# protoplank.net
KiCad netlist of a schematic drawn in EAGLE
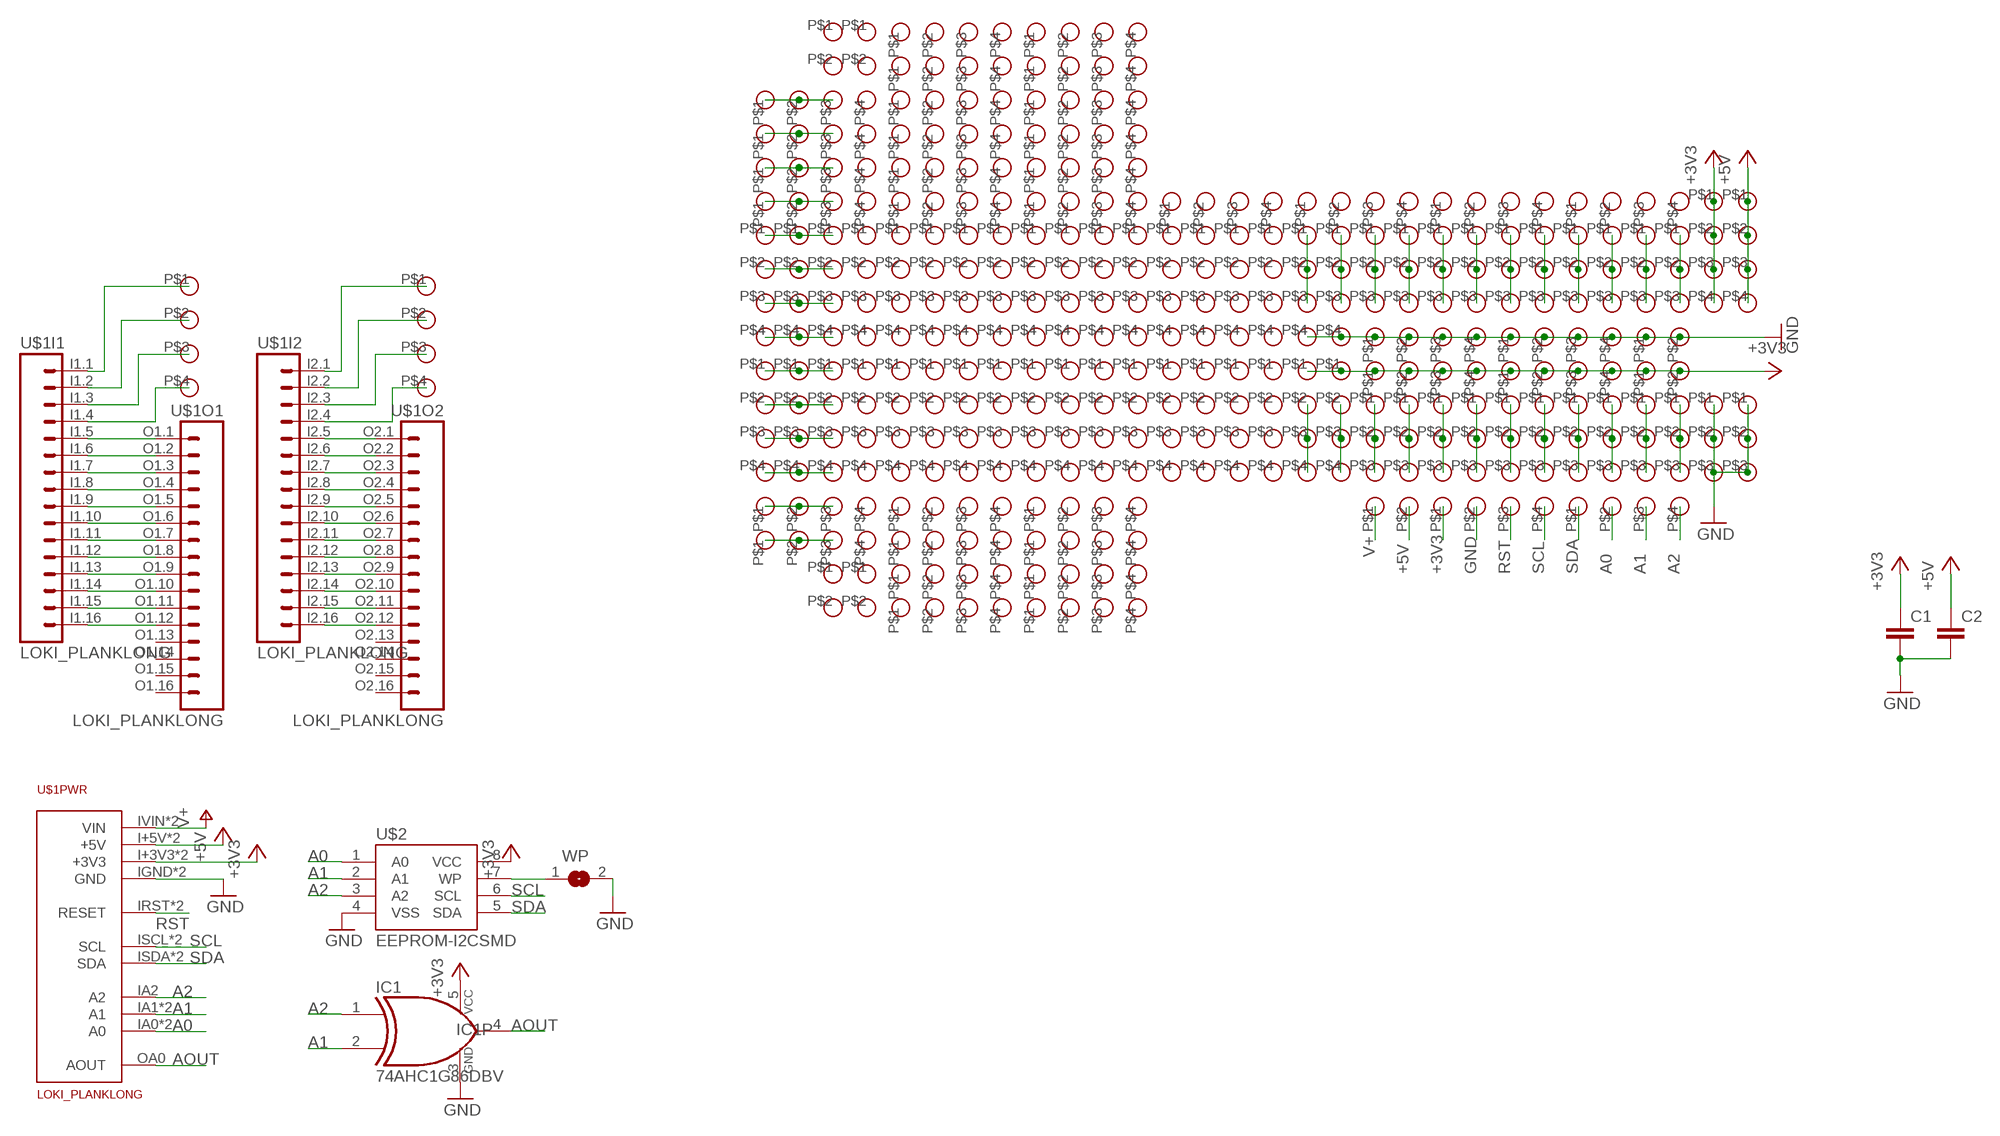
[diagram p0: schematic, sheet 1]

(export (version "E")
  (design (tool "Eeschema 10.0.6"))
  (components
    (comp (ref "C1")
      (value "CAPPTH")
      (footprint "eagle-import:CAP-PTH-SMALL")
      (libsource (lib "eagle-import") (part "CAPPTH"))
    )
    (comp (ref "C2")
      (value "CAPPTH")
      (footprint "eagle-import:CAP-PTH-SMALL")
      (libsource (lib "eagle-import") (part "CAPPTH"))
    )
    (comp (ref "IC1")
      (value "74AHC1G86DBV")
      (footprint "eagle-import:SOT23-5")
      (libsource (lib "eagle-import") (part "741G86DBVAHC"))
    )
    (comp (ref "U$1")
      (value "LOKI_PLANKLONG")
      (footprint "eagle-import:PLANK_LONG")
      (libsource (lib "eagle-import") (part "LOKI_PLANKLONG"))
    )
    (comp (ref "U$2")
      (value "EEPROM-I2CSMD")
      (footprint "eagle-import:SO08")
      (libsource (lib "eagle-import") (part "EEPROM-I2CSMD"))
    )
    (comp (ref "U$3")
      (value "PROTOPAD-3")
      (footprint "eagle-import:PROTOPAD-3")
      (libsource (lib "eagle-import") (part "PROTOPAD-3"))
    )
    (comp (ref "U$4")
      (value "PROTOPAD-3")
      (footprint "eagle-import:PROTOPAD-3")
      (libsource (lib "eagle-import") (part "PROTOPAD-3"))
    )
    (comp (ref "U$5")
      (value "PROTOPAD-3")
      (footprint "eagle-import:PROTOPAD-3")
      (libsource (lib "eagle-import") (part "PROTOPAD-3"))
    )
    (comp (ref "U$6")
      (value "PROTOPAD-3")
      (footprint "eagle-import:PROTOPAD-3")
      (libsource (lib "eagle-import") (part "PROTOPAD-3"))
    )
    (comp (ref "U$7")
      (value "PROTOPAD-3")
      (footprint "eagle-import:PROTOPAD-3")
      (libsource (lib "eagle-import") (part "PROTOPAD-3"))
    )
    (comp (ref "U$8")
      (value "PROTOPAD-3")
      (footprint "eagle-import:PROTOPAD-3")
      (libsource (lib "eagle-import") (part "PROTOPAD-3"))
    )
    (comp (ref "U$9")
      (value "PROTOPAD-3")
      (footprint "eagle-import:PROTOPAD-3")
      (libsource (lib "eagle-import") (part "PROTOPAD-3"))
    )
    (comp (ref "U$10")
      (value "PROTOPAD-3")
      (footprint "eagle-import:PROTOPAD-3")
      (libsource (lib "eagle-import") (part "PROTOPAD-3"))
    )
    (comp (ref "U$11")
      (value "PROTOPAD-3")
      (footprint "eagle-import:PROTOPAD-3")
      (libsource (lib "eagle-import") (part "PROTOPAD-3"))
    )
    (comp (ref "U$12")
      (value "PROTOPAD-3")
      (footprint "eagle-import:PROTOPAD-3")
      (libsource (lib "eagle-import") (part "PROTOPAD-3"))
    )
    (comp (ref "U$13")
      (value "PROTOPAD-3")
      (footprint "eagle-import:PROTOPAD-3")
      (libsource (lib "eagle-import") (part "PROTOPAD-3"))
    )
    (comp (ref "U$14")
      (value "PROTOPAD-3")
      (footprint "eagle-import:PROTOPAD-3")
      (libsource (lib "eagle-import") (part "PROTOPAD-3"))
    )
    (comp (ref "U$15")
      (value "PROTOPAD-3")
      (footprint "eagle-import:PROTOPAD-3")
      (libsource (lib "eagle-import") (part "PROTOPAD-3"))
    )
    (comp (ref "U$16")
      (value "PROTOPAD-3")
      (footprint "eagle-import:PROTOPAD-3")
      (libsource (lib "eagle-import") (part "PROTOPAD-3"))
    )
    (comp (ref "U$17")
      (value "PROTOPAD-3")
      (footprint "eagle-import:PROTOPAD-3")
      (libsource (lib "eagle-import") (part "PROTOPAD-3"))
    )
    (comp (ref "U$18")
      (value "PROTOPAD-3")
      (footprint "eagle-import:PROTOPAD-3")
      (libsource (lib "eagle-import") (part "PROTOPAD-3"))
    )
    (comp (ref "U$19")
      (value "PROTOPAD-3")
      (footprint "eagle-import:PROTOPAD-3")
      (libsource (lib "eagle-import") (part "PROTOPAD-3"))
    )
    (comp (ref "U$20")
      (value "PROTOPAD-3")
      (footprint "eagle-import:PROTOPAD-3")
      (libsource (lib "eagle-import") (part "PROTOPAD-3"))
    )
    (comp (ref "U$21")
      (value "PROTOPAD-3")
      (footprint "eagle-import:PROTOPAD-3")
      (libsource (lib "eagle-import") (part "PROTOPAD-3"))
    )
    (comp (ref "U$22")
      (value "PROTOPAD-3")
      (footprint "eagle-import:PROTOPAD-3")
      (libsource (lib "eagle-import") (part "PROTOPAD-3"))
    )
    (comp (ref "U$23")
      (value "PROTOPAD-4SQUARE")
      (footprint "eagle-import:PROTOPAD-4")
      (libsource (lib "eagle-import") (part "PROTOPAD-4SQUARE"))
    )
    (comp (ref "U$24")
      (value "PROTOPAD-4SQUARE")
      (footprint "eagle-import:PROTOPAD-4")
      (libsource (lib "eagle-import") (part "PROTOPAD-4SQUARE"))
    )
    (comp (ref "U$25")
      (value "PROTOPAD-4SQUARE")
      (footprint "eagle-import:PROTOPAD-4")
      (libsource (lib "eagle-import") (part "PROTOPAD-4SQUARE"))
    )
    (comp (ref "U$26")
      (value "PROTOPAD-4SQUARE")
      (footprint "eagle-import:PROTOPAD-4")
      (libsource (lib "eagle-import") (part "PROTOPAD-4SQUARE"))
    )
    (comp (ref "U$27")
      (value "PROTOPAD-2SQUARE")
      (footprint "eagle-import:PROTOPAD-2")
      (libsource (lib "eagle-import") (part "PROTOPAD-2SQUARE"))
    )
    (comp (ref "U$28")
      (value "PROTOPAD-2SQUARE")
      (footprint "eagle-import:PROTOPAD-2")
      (libsource (lib "eagle-import") (part "PROTOPAD-2SQUARE"))
    )
    (comp (ref "U$29")
      (value "PROTOPAD-4ROUND")
      (footprint "eagle-import:PROTOPAD-4-ROUND")
      (libsource (lib "eagle-import") (part "PROTOPAD-4ROUND"))
    )
    (comp (ref "U$30")
      (value "PROTOPAD-4ROUND")
      (footprint "eagle-import:PROTOPAD-4-ROUND")
      (libsource (lib "eagle-import") (part "PROTOPAD-4ROUND"))
    )
    (comp (ref "U$31")
      (value "PROTOPAD-4ROUND")
      (footprint "eagle-import:PROTOPAD-4-ROUND")
      (libsource (lib "eagle-import") (part "PROTOPAD-4ROUND"))
    )
    (comp (ref "U$32")
      (value "PROTOPAD-4ROUND")
      (footprint "eagle-import:PROTOPAD-4-ROUND")
      (libsource (lib "eagle-import") (part "PROTOPAD-4ROUND"))
    )
    (comp (ref "U$33")
      (value "PROTOPAD-2ROUND")
      (footprint "eagle-import:PROTOPAD-2-ROUND")
      (libsource (lib "eagle-import") (part "PROTOPAD-2ROUND"))
    )
    (comp (ref "U$34")
      (value "PROTOPAD-4SQUARE")
      (footprint "eagle-import:PROTOPAD-4")
      (libsource (lib "eagle-import") (part "PROTOPAD-4SQUARE"))
    )
    (comp (ref "U$35")
      (value "PROTOPAD-4SQUARE")
      (footprint "eagle-import:PROTOPAD-4")
      (libsource (lib "eagle-import") (part "PROTOPAD-4SQUARE"))
    )
    (comp (ref "U$36")
      (value "PROTOPAD-4SQUARE")
      (footprint "eagle-import:PROTOPAD-4")
      (libsource (lib "eagle-import") (part "PROTOPAD-4SQUARE"))
    )
    (comp (ref "U$37")
      (value "PROTOPAD-4SQUARE")
      (footprint "eagle-import:PROTOPAD-4")
      (libsource (lib "eagle-import") (part "PROTOPAD-4SQUARE"))
    )
    (comp (ref "U$38")
      (value "PROTOPAD-4SQUARE")
      (footprint "eagle-import:PROTOPAD-4")
      (libsource (lib "eagle-import") (part "PROTOPAD-4SQUARE"))
    )
    (comp (ref "U$39")
      (value "PROTOPAD-4SQUARE")
      (footprint "eagle-import:PROTOPAD-4")
      (libsource (lib "eagle-import") (part "PROTOPAD-4SQUARE"))
    )
    (comp (ref "U$40")
      (value "PROTOPAD-4SQUARE")
      (footprint "eagle-import:PROTOPAD-4")
      (libsource (lib "eagle-import") (part "PROTOPAD-4SQUARE"))
    )
    (comp (ref "U$41")
      (value "PROTOPAD-4SQUARE")
      (footprint "eagle-import:PROTOPAD-4")
      (libsource (lib "eagle-import") (part "PROTOPAD-4SQUARE"))
    )
    (comp (ref "U$42")
      (value "PROTOPAD-4SQUARE")
      (footprint "eagle-import:PROTOPAD-4")
      (libsource (lib "eagle-import") (part "PROTOPAD-4SQUARE"))
    )
    (comp (ref "U$43")
      (value "PROTOPAD-4SQUARE")
      (footprint "eagle-import:PROTOPAD-4")
      (libsource (lib "eagle-import") (part "PROTOPAD-4SQUARE"))
    )
    (comp (ref "U$44")
      (value "PROTOPAD-4SQUARE")
      (footprint "eagle-import:PROTOPAD-4")
      (libsource (lib "eagle-import") (part "PROTOPAD-4SQUARE"))
    )
    (comp (ref "U$45")
      (value "PROTOPAD-4SQUARE")
      (footprint "eagle-import:PROTOPAD-4")
      (libsource (lib "eagle-import") (part "PROTOPAD-4SQUARE"))
    )
    (comp (ref "U$46")
      (value "PROTOPAD-4SQUARE")
      (footprint "eagle-import:PROTOPAD-4")
      (libsource (lib "eagle-import") (part "PROTOPAD-4SQUARE"))
    )
    (comp (ref "U$47")
      (value "PROTOPAD-4SQUARE")
      (footprint "eagle-import:PROTOPAD-4")
      (libsource (lib "eagle-import") (part "PROTOPAD-4SQUARE"))
    )
    (comp (ref "U$48")
      (value "PROTOPAD-4SQUARE")
      (footprint "eagle-import:PROTOPAD-4")
      (libsource (lib "eagle-import") (part "PROTOPAD-4SQUARE"))
    )
    (comp (ref "U$49")
      (value "PROTOPAD-4SQUARE")
      (footprint "eagle-import:PROTOPAD-4")
      (libsource (lib "eagle-import") (part "PROTOPAD-4SQUARE"))
    )
    (comp (ref "U$50")
      (value "PROTOPAD-4SQUARE")
      (footprint "eagle-import:PROTOPAD-4")
      (libsource (lib "eagle-import") (part "PROTOPAD-4SQUARE"))
    )
    (comp (ref "U$51")
      (value "PROTOPAD-4SQUARE")
      (footprint "eagle-import:PROTOPAD-4")
      (libsource (lib "eagle-import") (part "PROTOPAD-4SQUARE"))
    )
    (comp (ref "U$52")
      (value "PROTOPAD-4SQUARE")
      (footprint "eagle-import:PROTOPAD-4")
      (libsource (lib "eagle-import") (part "PROTOPAD-4SQUARE"))
    )
    (comp (ref "U$53")
      (value "PROTOPAD-4SQUARE")
      (footprint "eagle-import:PROTOPAD-4")
      (libsource (lib "eagle-import") (part "PROTOPAD-4SQUARE"))
    )
    (comp (ref "U$54")
      (value "PROTOPAD-4SQUARE")
      (footprint "eagle-import:PROTOPAD-4")
      (libsource (lib "eagle-import") (part "PROTOPAD-4SQUARE"))
    )
    (comp (ref "U$55")
      (value "PROTOPAD-4SQUARE")
      (footprint "eagle-import:PROTOPAD-4")
      (libsource (lib "eagle-import") (part "PROTOPAD-4SQUARE"))
    )
    (comp (ref "U$56")
      (value "PROTOPAD-4SQUARE")
      (footprint "eagle-import:PROTOPAD-4")
      (libsource (lib "eagle-import") (part "PROTOPAD-4SQUARE"))
    )
    (comp (ref "U$57")
      (value "PROTOPAD-4SQUARE")
      (footprint "eagle-import:PROTOPAD-4")
      (libsource (lib "eagle-import") (part "PROTOPAD-4SQUARE"))
    )
    (comp (ref "U$58")
      (value "PROTOPAD-4SQUARE")
      (footprint "eagle-import:PROTOPAD-4")
      (libsource (lib "eagle-import") (part "PROTOPAD-4SQUARE"))
    )
    (comp (ref "U$59")
      (value "PROTOPAD-4SQUARE")
      (footprint "eagle-import:PROTOPAD-4")
      (libsource (lib "eagle-import") (part "PROTOPAD-4SQUARE"))
    )
    (comp (ref "U$60")
      (value "PROTOPAD-4SQUARE")
      (footprint "eagle-import:PROTOPAD-4")
      (libsource (lib "eagle-import") (part "PROTOPAD-4SQUARE"))
    )
    (comp (ref "U$61")
      (value "PROTOPAD-4SQUARE")
      (footprint "eagle-import:PROTOPAD-4")
      (libsource (lib "eagle-import") (part "PROTOPAD-4SQUARE"))
    )
    (comp (ref "U$62")
      (value "PROTOPAD-4SQUARE")
      (footprint "eagle-import:PROTOPAD-4")
      (libsource (lib "eagle-import") (part "PROTOPAD-4SQUARE"))
    )
    (comp (ref "U$63")
      (value "PROTOPAD-4SQUARE")
      (footprint "eagle-import:PROTOPAD-4")
      (libsource (lib "eagle-import") (part "PROTOPAD-4SQUARE"))
    )
    (comp (ref "U$64")
      (value "PROTOPAD-4SQUARE")
      (footprint "eagle-import:PROTOPAD-4")
      (libsource (lib "eagle-import") (part "PROTOPAD-4SQUARE"))
    )
    (comp (ref "U$65")
      (value "PROTOPAD-4SQUARE")
      (footprint "eagle-import:PROTOPAD-4")
      (libsource (lib "eagle-import") (part "PROTOPAD-4SQUARE"))
    )
    (comp (ref "U$66")
      (value "PROTOPAD-4SQUARE")
      (footprint "eagle-import:PROTOPAD-4")
      (libsource (lib "eagle-import") (part "PROTOPAD-4SQUARE"))
    )
    (comp (ref "U$67")
      (value "PROTOPAD-4SQUARE")
      (footprint "eagle-import:PROTOPAD-4")
      (libsource (lib "eagle-import") (part "PROTOPAD-4SQUARE"))
    )
    (comp (ref "U$68")
      (value "PROTOPAD-4SQUARE")
      (footprint "eagle-import:PROTOPAD-4")
      (libsource (lib "eagle-import") (part "PROTOPAD-4SQUARE"))
    )
    (comp (ref "U$69")
      (value "PROTOPAD-4SQUARE")
      (footprint "eagle-import:PROTOPAD-4")
      (libsource (lib "eagle-import") (part "PROTOPAD-4SQUARE"))
    )
    (comp (ref "U$70")
      (value "PROTOPAD-4SQUARE")
      (footprint "eagle-import:PROTOPAD-4")
      (libsource (lib "eagle-import") (part "PROTOPAD-4SQUARE"))
    )
    (comp (ref "U$71")
      (value "PROTOPAD-4SQUARE")
      (footprint "eagle-import:PROTOPAD-4")
      (libsource (lib "eagle-import") (part "PROTOPAD-4SQUARE"))
    )
    (comp (ref "U$72")
      (value "PROTOPAD-4SQUARE")
      (footprint "eagle-import:PROTOPAD-4")
      (libsource (lib "eagle-import") (part "PROTOPAD-4SQUARE"))
    )
    (comp (ref "U$73")
      (value "PROTOPAD-4SQUARE")
      (footprint "eagle-import:PROTOPAD-4")
      (libsource (lib "eagle-import") (part "PROTOPAD-4SQUARE"))
    )
    (comp (ref "U$74")
      (value "PROTOPAD-4SQUARE")
      (footprint "eagle-import:PROTOPAD-4")
      (libsource (lib "eagle-import") (part "PROTOPAD-4SQUARE"))
    )
    (comp (ref "U$75")
      (value "PROTOPAD-4SQUARE")
      (footprint "eagle-import:PROTOPAD-4")
      (libsource (lib "eagle-import") (part "PROTOPAD-4SQUARE"))
    )
    (comp (ref "U$76")
      (value "PROTOPAD-4SQUARE")
      (footprint "eagle-import:PROTOPAD-4")
      (libsource (lib "eagle-import") (part "PROTOPAD-4SQUARE"))
    )
    (comp (ref "U$77")
      (value "PROTOPAD-4SQUARE")
      (footprint "eagle-import:PROTOPAD-4")
      (libsource (lib "eagle-import") (part "PROTOPAD-4SQUARE"))
    )
    (comp (ref "U$78")
      (value "PROTOPAD-3")
      (footprint "eagle-import:PROTOPAD-3")
      (libsource (lib "eagle-import") (part "PROTOPAD-3"))
    )
    (comp (ref "U$79")
      (value "PROTOPAD-4SQUARE")
      (footprint "eagle-import:PROTOPAD-4")
      (libsource (lib "eagle-import") (part "PROTOPAD-4SQUARE"))
    )
    (comp (ref "U$80")
      (value "PROTOPAD-3")
      (footprint "eagle-import:PROTOPAD-3")
      (libsource (lib "eagle-import") (part "PROTOPAD-3"))
    )
    (comp (ref "U$81")
      (value "PROTOPAD-4SQUARE")
      (footprint "eagle-import:PROTOPAD-4")
      (libsource (lib "eagle-import") (part "PROTOPAD-4SQUARE"))
    )
    (comp (ref "U$82")
      (value "PROTOPAD-4SQUARE")
      (footprint "eagle-import:PROTOPAD-4")
      (libsource (lib "eagle-import") (part "PROTOPAD-4SQUARE"))
    )
    (comp (ref "U$83")
      (value "PROTOPAD-4SQUARE")
      (footprint "eagle-import:PROTOPAD-4")
      (libsource (lib "eagle-import") (part "PROTOPAD-4SQUARE"))
    )
    (comp (ref "U$84")
      (value "PROTOPAD-4SQUARE")
      (footprint "eagle-import:PROTOPAD-4")
      (libsource (lib "eagle-import") (part "PROTOPAD-4SQUARE"))
    )
    (comp (ref "U$85")
      (value "PROTOPAD-4SQUARE")
      (footprint "eagle-import:PROTOPAD-4")
      (libsource (lib "eagle-import") (part "PROTOPAD-4SQUARE"))
    )
    (comp (ref "U$86")
      (value "PROTOPAD-4SQUARE")
      (footprint "eagle-import:PROTOPAD-4")
      (libsource (lib "eagle-import") (part "PROTOPAD-4SQUARE"))
    )
    (comp (ref "U$87")
      (value "PROTOPAD-4SQUARE")
      (footprint "eagle-import:PROTOPAD-4")
      (libsource (lib "eagle-import") (part "PROTOPAD-4SQUARE"))
    )
    (comp (ref "U$88")
      (value "PROTOPAD-4SQUARE")
      (footprint "eagle-import:PROTOPAD-4")
      (libsource (lib "eagle-import") (part "PROTOPAD-4SQUARE"))
    )
    (comp (ref "U$89")
      (value "PROTOPAD-4SQUARE")
      (footprint "eagle-import:PROTOPAD-4")
      (libsource (lib "eagle-import") (part "PROTOPAD-4SQUARE"))
    )
    (comp (ref "U$90")
      (value "PROTOPAD-4SQUARE")
      (footprint "eagle-import:PROTOPAD-4")
      (libsource (lib "eagle-import") (part "PROTOPAD-4SQUARE"))
    )
    (comp (ref "U$91")
      (value "PROTOPAD-4SQUARE")
      (footprint "eagle-import:PROTOPAD-4")
      (libsource (lib "eagle-import") (part "PROTOPAD-4SQUARE"))
    )
    (comp (ref "U$92")
      (value "PROTOPAD-4SQUARE")
      (footprint "eagle-import:PROTOPAD-4")
      (libsource (lib "eagle-import") (part "PROTOPAD-4SQUARE"))
    )
    (comp (ref "U$93")
      (value "PROTOPAD-4SQUARE")
      (footprint "eagle-import:PROTOPAD-4")
      (libsource (lib "eagle-import") (part "PROTOPAD-4SQUARE"))
    )
    (comp (ref "U$94")
      (value "PROTOPAD-4SQUARE")
      (footprint "eagle-import:PROTOPAD-4")
      (libsource (lib "eagle-import") (part "PROTOPAD-4SQUARE"))
    )
    (comp (ref "U$95")
      (value "PROTOPAD-4SQUARE")
      (footprint "eagle-import:PROTOPAD-4")
      (libsource (lib "eagle-import") (part "PROTOPAD-4SQUARE"))
    )
    (comp (ref "U$96")
      (value "PROTOPAD-4SQUARE")
      (footprint "eagle-import:PROTOPAD-4")
      (libsource (lib "eagle-import") (part "PROTOPAD-4SQUARE"))
    )
    (comp (ref "U$97")
      (value "PROTOPAD-4SQUARE")
      (footprint "eagle-import:PROTOPAD-4")
      (libsource (lib "eagle-import") (part "PROTOPAD-4SQUARE"))
    )
    (comp (ref "U$98")
      (value "PROTOPAD-4SQUARE")
      (footprint "eagle-import:PROTOPAD-4")
      (libsource (lib "eagle-import") (part "PROTOPAD-4SQUARE"))
    )
    (comp (ref "U$99")
      (value "PROTOPAD-4SQUARE")
      (footprint "eagle-import:PROTOPAD-4")
      (libsource (lib "eagle-import") (part "PROTOPAD-4SQUARE"))
    )
    (comp (ref "U$100")
      (value "PROTOPAD-4SQUARE")
      (footprint "eagle-import:PROTOPAD-4")
      (libsource (lib "eagle-import") (part "PROTOPAD-4SQUARE"))
    )
    (comp (ref "U$101")
      (value "PROTOPAD-4SQUARE")
      (footprint "eagle-import:PROTOPAD-4")
      (libsource (lib "eagle-import") (part "PROTOPAD-4SQUARE"))
    )
    (comp (ref "U$102")
      (value "PROTOPAD-4SQUARE")
      (footprint "eagle-import:PROTOPAD-4")
      (libsource (lib "eagle-import") (part "PROTOPAD-4SQUARE"))
    )
    (comp (ref "U$103")
      (value "PROTOPAD-4SQUARE")
      (footprint "eagle-import:PROTOPAD-4")
      (libsource (lib "eagle-import") (part "PROTOPAD-4SQUARE"))
    )
    (comp (ref "U$104")
      (value "PROTOPAD-2SQUARE")
      (footprint "eagle-import:PROTOPAD-2")
      (libsource (lib "eagle-import") (part "PROTOPAD-2SQUARE"))
    )
    (comp (ref "U$105")
      (value "PROTOPAD-2SQUARE")
      (footprint "eagle-import:PROTOPAD-2")
      (libsource (lib "eagle-import") (part "PROTOPAD-2SQUARE"))
    )
    (comp (ref "U$106")
      (value "PROTOPAD-2SQUARE")
      (footprint "eagle-import:PROTOPAD-2")
      (libsource (lib "eagle-import") (part "PROTOPAD-2SQUARE"))
    )
    (comp (ref "U$107")
      (value "PROTOPAD-2SQUARE")
      (footprint "eagle-import:PROTOPAD-2")
      (libsource (lib "eagle-import") (part "PROTOPAD-2SQUARE"))
    )
    (comp (ref "WP") (value "SJ") (footprint "eagle-import:SJ") (libsource (lib "eagle-import") (part "SJ")))
  )
  (nets
    (net (code "1") (name "+3V3") (class "Default")
      (node (ref "C1") (pin "1") (pinfunction "1_1") (pintype "passive"))
      (node (ref "IC1") (pin "5") (pinfunction "VCC_5") (pintype "power_in"))
      (node (ref "U$1") (pin "I+3V3") (pinfunction "+3V3_I+3V3") (pintype "power_in"))
      (node (ref "U$1") (pin "O+3V3") (pinfunction "+3V3_O+3V3") (pintype "power_in"))
      (node (ref "U$2") (pin "8") (pinfunction "VCC_8") (pintype "power_in"))
      (node (ref "U$25") (pin "P$1") (pinfunction "P$1_P$1") (pintype "passive"))
      (node (ref "U$25") (pin "P$2") (pinfunction "P$2_P$2") (pintype "passive"))
      (node (ref "U$25") (pin "P$3") (pinfunction "P$3_P$3") (pintype "passive"))
      (node (ref "U$25") (pin "P$4") (pinfunction "P$4_P$4") (pintype "passive"))
      (node (ref "U$26") (pin "P$1") (pinfunction "P$1_P$1") (pintype "passive"))
      (node (ref "U$26") (pin "P$2") (pinfunction "P$2_P$2") (pintype "passive"))
      (node (ref "U$26") (pin "P$3") (pinfunction "P$3_P$3") (pintype "passive"))
      (node (ref "U$26") (pin "P$4") (pinfunction "P$4_P$4") (pintype "passive"))
      (node (ref "U$28") (pin "P$1") (pinfunction "P$1_P$1") (pintype "passive"))
      (node (ref "U$28") (pin "P$2") (pinfunction "P$2_P$2") (pintype "passive"))
      (node (ref "U$32") (pin "P$1") (pinfunction "P$1_P$1") (pintype "passive"))
      (node (ref "U$35") (pin "P$1") (pinfunction "P$1_P$1") (pintype "passive"))
      (node (ref "U$36") (pin "P$1") (pinfunction "P$1_P$1") (pintype "passive"))
      (node (ref "U$77") (pin "P$1") (pinfunction "P$1_P$1") (pintype "passive"))
      (node (ref "U$77") (pin "P$2") (pinfunction "P$2_P$2") (pintype "passive"))
      (node (ref "U$77") (pin "P$3") (pinfunction "P$3_P$3") (pintype "passive"))
      (node (ref "U$77") (pin "P$4") (pinfunction "P$4_P$4") (pintype "passive"))
    )
    (net (code "2") (name "+5V") (class "Default")
      (node (ref "C2") (pin "1") (pinfunction "1_1") (pintype "passive"))
      (node (ref "U$1") (pin "I+5V") (pinfunction "+5V_I+5V") (pintype "power_in"))
      (node (ref "U$1") (pin "O+5V") (pinfunction "+5V_O+5V") (pintype "power_in"))
      (node (ref "U$33") (pin "P$2") (pinfunction "P$2_P$2") (pintype "passive"))
      (node (ref "U$79") (pin "P$1") (pinfunction "P$1_P$1") (pintype "passive"))
      (node (ref "U$79") (pin "P$2") (pinfunction "P$2_P$2") (pintype "passive"))
      (node (ref "U$79") (pin "P$3") (pinfunction "P$3_P$3") (pintype "passive"))
      (node (ref "U$79") (pin "P$4") (pinfunction "P$4_P$4") (pintype "passive"))
    )
    (net (code "3") (name "/A0") (class "Default")
      (node (ref "U$1") (pin "IA0") (pinfunction "A0_IA0") (pintype "output"))
      (node (ref "U$1") (pin "OA1") (pinfunction "A0_OA1") (pintype "output"))
      (node (ref "U$2") (pin "1") (pinfunction "A0_1") (pintype "bidirectional"))
      (node (ref "U$31") (pin "P$2") (pinfunction "P$2_P$2") (pintype "passive"))
    )
    (net (code "4") (name "/A1") (class "Default")
      (node (ref "IC1") (pin "2") (pinfunction "I1_2") (pintype "input"))
      (node (ref "U$1") (pin "IA1") (pinfunction "A1_IA1") (pintype "output"))
      (node (ref "U$1") (pin "OA2") (pinfunction "A1_OA2") (pintype "output"))
      (node (ref "U$2") (pin "2") (pinfunction "A1_2") (pintype "bidirectional"))
      (node (ref "U$31") (pin "P$3") (pinfunction "P$3_P$3") (pintype "passive"))
    )
    (net (code "5") (name "/A2") (class "Default")
      (node (ref "IC1") (pin "1") (pinfunction "I0_1") (pintype "input"))
      (node (ref "U$1") (pin "IA2") (pinfunction "A2_IA2") (pintype "output"))
      (node (ref "U$2") (pin "3") (pinfunction "A2_3") (pintype "bidirectional"))
      (node (ref "U$31") (pin "P$4") (pinfunction "P$4_P$4") (pintype "passive"))
    )
    (net (code "6") (name "/AOUT") (class "Default")
      (node (ref "IC1") (pin "4") (pinfunction "O_4") (pintype "output"))
      (node (ref "U$1") (pin "OA0") (pinfunction "AOUT_OA0") (pintype "input"))
    )
    (net (code "7") (name "/RST") (class "Default")
      (node (ref "U$1") (pin "IRST") (pinfunction "RESET_IRST") (pintype "input"))
      (node (ref "U$1") (pin "ORST") (pinfunction "RESET_ORST") (pintype "input"))
      (node (ref "U$32") (pin "P$3") (pinfunction "P$3_P$3") (pintype "passive"))
    )
    (net (code "8") (name "/SCL") (class "Default")
      (node (ref "U$1") (pin "ISCL") (pinfunction "SCL_ISCL") (pintype "bidirectional"))
      (node (ref "U$1") (pin "OSCL") (pinfunction "SCL_OSCL") (pintype "bidirectional"))
      (node (ref "U$2") (pin "6") (pinfunction "SCL_6") (pintype "bidirectional"))
      (node (ref "U$32") (pin "P$4") (pinfunction "P$4_P$4") (pintype "passive"))
    )
    (net (code "9") (name "/SDA") (class "Default")
      (node (ref "U$1") (pin "ISDA") (pinfunction "SDA_ISDA") (pintype "bidirectional"))
      (node (ref "U$1") (pin "OSDA") (pinfunction "SDA_OSDA") (pintype "bidirectional"))
      (node (ref "U$2") (pin "5") (pinfunction "SDA_5") (pintype "bidirectional"))
      (node (ref "U$31") (pin "P$1") (pinfunction "P$1_P$1") (pintype "passive"))
    )
    (net (code "10") (name "GND") (class "Default")
      (node (ref "C1") (pin "2") (pinfunction "2_2") (pintype "passive"))
      (node (ref "C2") (pin "2") (pinfunction "2_2") (pintype "passive"))
      (node (ref "IC1") (pin "3") (pinfunction "GND_3") (pintype "power_in"))
      (node (ref "U$1") (pin "IGND") (pinfunction "GND_IGND") (pintype "power_in"))
      (node (ref "U$1") (pin "OGND") (pinfunction "GND_OGND") (pintype "power_in"))
      (node (ref "U$2") (pin "4") (pinfunction "VSS_4") (pintype "power_in"))
      (node (ref "U$23") (pin "P$1") (pinfunction "P$1_P$1") (pintype "passive"))
      (node (ref "U$23") (pin "P$2") (pinfunction "P$2_P$2") (pintype "passive"))
      (node (ref "U$23") (pin "P$3") (pinfunction "P$3_P$3") (pintype "passive"))
      (node (ref "U$23") (pin "P$4") (pinfunction "P$4_P$4") (pintype "passive"))
      (node (ref "U$24") (pin "P$1") (pinfunction "P$1_P$1") (pintype "passive"))
      (node (ref "U$24") (pin "P$2") (pinfunction "P$2_P$2") (pintype "passive"))
      (node (ref "U$24") (pin "P$3") (pinfunction "P$3_P$3") (pintype "passive"))
      (node (ref "U$24") (pin "P$4") (pinfunction "P$4_P$4") (pintype "passive"))
      (node (ref "U$27") (pin "P$1") (pinfunction "P$1_P$1") (pintype "passive"))
      (node (ref "U$27") (pin "P$2") (pinfunction "P$2_P$2") (pintype "passive"))
      (node (ref "U$32") (pin "P$2") (pinfunction "P$2_P$2") (pintype "passive"))
      (node (ref "U$34") (pin "P$4") (pinfunction "P$4_P$4") (pintype "passive"))
      (node (ref "U$37") (pin "P$4") (pinfunction "P$4_P$4") (pintype "passive"))
      (node (ref "U$78") (pin "P$1") (pinfunction "P$1_P$1") (pintype "passive"))
      (node (ref "U$78") (pin "P$2") (pinfunction "P$2_P$2") (pintype "passive"))
      (node (ref "U$78") (pin "P$3") (pinfunction "P$3_P$3") (pintype "passive"))
      (node (ref "U$80") (pin "P$1") (pinfunction "P$1_P$1") (pintype "passive"))
      (node (ref "U$80") (pin "P$2") (pinfunction "P$2_P$2") (pintype "passive"))
      (node (ref "U$80") (pin "P$3") (pinfunction "P$3_P$3") (pintype "passive"))
      (node (ref "WP") (pin "2") (pinfunction "2_2") (pintype "passive"))
    )
    (net (code "11") (name "Net-(U$1A-1)") (class "Default")
      (node (ref "U$1") (pin "I1.1") (pinfunction "1_I1.1") (pintype "passive"))
      (node (ref "U$29") (pin "P$1") (pinfunction "P$1_P$1") (pintype "passive"))
    )
    (net (code "12") (name "Net-(U$1A-2)") (class "Default")
      (node (ref "U$1") (pin "I1.2") (pinfunction "2_I1.2") (pintype "passive"))
      (node (ref "U$29") (pin "P$2") (pinfunction "P$2_P$2") (pintype "passive"))
    )
    (net (code "13") (name "Net-(U$1A-3)") (class "Default")
      (node (ref "U$1") (pin "I1.3") (pinfunction "3_I1.3") (pintype "passive"))
      (node (ref "U$29") (pin "P$3") (pinfunction "P$3_P$3") (pintype "passive"))
    )
    (net (code "14") (name "Net-(U$1A-4)") (class "Default")
      (node (ref "U$1") (pin "I1.4") (pinfunction "4_I1.4") (pintype "passive"))
      (node (ref "U$29") (pin "P$4") (pinfunction "P$4_P$4") (pintype "passive"))
    )
    (net (code "15") (name "Net-(U$1A-5)") (class "Default")
      (node (ref "U$1") (pin "I1.5") (pinfunction "5_I1.5") (pintype "passive"))
      (node (ref "U$1") (pin "O1.1") (pinfunction "1_O1.1") (pintype "passive"))
    )
    (net (code "16") (name "Net-(U$1A-6)") (class "Default")
      (node (ref "U$1") (pin "I1.6") (pinfunction "6_I1.6") (pintype "passive"))
      (node (ref "U$1") (pin "O1.2") (pinfunction "2_O1.2") (pintype "passive"))
    )
    (net (code "17") (name "Net-(U$1A-7)") (class "Default")
      (node (ref "U$1") (pin "I1.7") (pinfunction "7_I1.7") (pintype "passive"))
      (node (ref "U$1") (pin "O1.3") (pinfunction "3_O1.3") (pintype "passive"))
    )
    (net (code "18") (name "Net-(U$1A-8)") (class "Default")
      (node (ref "U$1") (pin "I1.8") (pinfunction "8_I1.8") (pintype "passive"))
      (node (ref "U$1") (pin "O1.4") (pinfunction "4_O1.4") (pintype "passive"))
    )
    (net (code "19") (name "Net-(U$1A-9)") (class "Default")
      (node (ref "U$1") (pin "I1.9") (pinfunction "9_I1.9") (pintype "passive"))
      (node (ref "U$1") (pin "O1.5") (pinfunction "5_O1.5") (pintype "passive"))
    )
    (net (code "20") (name "Net-(U$1A-10)") (class "Default")
      (node (ref "U$1") (pin "I1.10") (pinfunction "10_I1.10") (pintype "passive"))
      (node (ref "U$1") (pin "O1.6") (pinfunction "6_O1.6") (pintype "passive"))
    )
    (net (code "21") (name "Net-(U$1A-11)") (class "Default")
      (node (ref "U$1") (pin "I1.11") (pinfunction "11_I1.11") (pintype "passive"))
      (node (ref "U$1") (pin "O1.7") (pinfunction "7_O1.7") (pintype "passive"))
    )
    (net (code "22") (name "Net-(U$1A-12)") (class "Default")
      (node (ref "U$1") (pin "I1.12") (pinfunction "12_I1.12") (pintype "passive"))
      (node (ref "U$1") (pin "O1.8") (pinfunction "8_O1.8") (pintype "passive"))
    )
    (net (code "23") (name "Net-(U$1A-13)") (class "Default")
      (node (ref "U$1") (pin "I1.13") (pinfunction "13_I1.13") (pintype "passive"))
      (node (ref "U$1") (pin "O1.9") (pinfunction "9_O1.9") (pintype "passive"))
    )
    (net (code "24") (name "Net-(U$1A-14)") (class "Default")
      (node (ref "U$1") (pin "I1.14") (pinfunction "14_I1.14") (pintype "passive"))
      (node (ref "U$1") (pin "O1.10") (pinfunction "10_O1.10") (pintype "passive"))
    )
    (net (code "25") (name "Net-(U$1A-15)") (class "Default")
      (node (ref "U$1") (pin "I1.15") (pinfunction "15_I1.15") (pintype "passive"))
      (node (ref "U$1") (pin "O1.11") (pinfunction "11_O1.11") (pintype "passive"))
    )
    (net (code "26") (name "Net-(U$1A-16)") (class "Default")
      (node (ref "U$1") (pin "I1.16") (pinfunction "16_I1.16") (pintype "passive"))
      (node (ref "U$1") (pin "O1.12") (pinfunction "12_O1.12") (pintype "passive"))
    )
    (net (code "27") (name "Net-(U$1B-1)") (class "Default")
      (node (ref "U$1") (pin "I2.1") (pinfunction "1_I2.1") (pintype "passive"))
      (node (ref "U$30") (pin "P$1") (pinfunction "P$1_P$1") (pintype "passive"))
    )
    (net (code "28") (name "Net-(U$1B-2)") (class "Default")
      (node (ref "U$1") (pin "I2.2") (pinfunction "2_I2.2") (pintype "passive"))
      (node (ref "U$30") (pin "P$2") (pinfunction "P$2_P$2") (pintype "passive"))
    )
    (net (code "29") (name "Net-(U$1B-3)") (class "Default")
      (node (ref "U$1") (pin "I2.3") (pinfunction "3_I2.3") (pintype "passive"))
      (node (ref "U$30") (pin "P$3") (pinfunction "P$3_P$3") (pintype "passive"))
    )
    (net (code "30") (name "Net-(U$1B-4)") (class "Default")
      (node (ref "U$1") (pin "I2.4") (pinfunction "4_I2.4") (pintype "passive"))
      (node (ref "U$30") (pin "P$4") (pinfunction "P$4_P$4") (pintype "passive"))
    )
    (net (code "31") (name "Net-(U$1B-5)") (class "Default")
      (node (ref "U$1") (pin "I2.5") (pinfunction "5_I2.5") (pintype "passive"))
      (node (ref "U$1") (pin "O2.1") (pinfunction "1_O2.1") (pintype "passive"))
    )
    (net (code "32") (name "Net-(U$1B-6)") (class "Default")
      (node (ref "U$1") (pin "I2.6") (pinfunction "6_I2.6") (pintype "passive"))
      (node (ref "U$1") (pin "O2.2") (pinfunction "2_O2.2") (pintype "passive"))
    )
    (net (code "33") (name "Net-(U$1B-7)") (class "Default")
      (node (ref "U$1") (pin "I2.7") (pinfunction "7_I2.7") (pintype "passive"))
      (node (ref "U$1") (pin "O2.3") (pinfunction "3_O2.3") (pintype "passive"))
    )
    (net (code "34") (name "Net-(U$1B-8)") (class "Default")
      (node (ref "U$1") (pin "I2.8") (pinfunction "8_I2.8") (pintype "passive"))
      (node (ref "U$1") (pin "O2.4") (pinfunction "4_O2.4") (pintype "passive"))
    )
    (net (code "35") (name "Net-(U$1B-9)") (class "Default")
      (node (ref "U$1") (pin "I2.9") (pinfunction "9_I2.9") (pintype "passive"))
      (node (ref "U$1") (pin "O2.5") (pinfunction "5_O2.5") (pintype "passive"))
    )
    (net (code "36") (name "Net-(U$1B-10)") (class "Default")
      (node (ref "U$1") (pin "I2.10") (pinfunction "10_I2.10") (pintype "passive"))
      (node (ref "U$1") (pin "O2.6") (pinfunction "6_O2.6") (pintype "passive"))
    )
    (net (code "37") (name "Net-(U$1B-11)") (class "Default")
      (node (ref "U$1") (pin "I2.11") (pinfunction "11_I2.11") (pintype "passive"))
      (node (ref "U$1") (pin "O2.7") (pinfunction "7_O2.7") (pintype "passive"))
    )
    (net (code "38") (name "Net-(U$1B-12)") (class "Default")
      (node (ref "U$1") (pin "I2.12") (pinfunction "12_I2.12") (pintype "passive"))
      (node (ref "U$1") (pin "O2.8") (pinfunction "8_O2.8") (pintype "passive"))
    )
    (net (code "39") (name "Net-(U$1B-13)") (class "Default")
      (node (ref "U$1") (pin "I2.13") (pinfunction "13_I2.13") (pintype "passive"))
      (node (ref "U$1") (pin "O2.9") (pinfunction "9_O2.9") (pintype "passive"))
    )
    (net (code "40") (name "Net-(U$1B-14)") (class "Default")
      (node (ref "U$1") (pin "I2.14") (pinfunction "14_I2.14") (pintype "passive"))
      (node (ref "U$1") (pin "O2.10") (pinfunction "10_O2.10") (pintype "passive"))
    )
    (net (code "41") (name "Net-(U$1B-15)") (class "Default")
      (node (ref "U$1") (pin "I2.15") (pinfunction "15_I2.15") (pintype "passive"))
      (node (ref "U$1") (pin "O2.11") (pinfunction "11_O2.11") (pintype "passive"))
    )
    (net (code "42") (name "Net-(U$1B-16)") (class "Default")
      (node (ref "U$1") (pin "I2.16") (pinfunction "16_I2.16") (pintype "passive"))
      (node (ref "U$1") (pin "O2.12") (pinfunction "12_O2.12") (pintype "passive"))
    )
    (net (code "43") (name "Net-(U$2-WP)") (class "Default")
      (node (ref "U$2") (pin "7") (pinfunction "WP_7") (pintype "bidirectional"))
      (node (ref "WP") (pin "1") (pinfunction "1_1") (pintype "passive"))
    )
    (net (code "44") (name "Net-(U$3-PadP$1)") (class "Default")
      (node (ref "U$3") (pin "P$1") (pinfunction "P$1_P$1") (pintype "passive"))
      (node (ref "U$3") (pin "P$2") (pinfunction "P$2_P$2") (pintype "passive"))
      (node (ref "U$3") (pin "P$3") (pinfunction "P$3_P$3") (pintype "passive"))
    )
    (net (code "45") (name "Net-(U$4-PadP$1)") (class "Default")
      (node (ref "U$4") (pin "P$1") (pinfunction "P$1_P$1") (pintype "passive"))
      (node (ref "U$4") (pin "P$2") (pinfunction "P$2_P$2") (pintype "passive"))
      (node (ref "U$4") (pin "P$3") (pinfunction "P$3_P$3") (pintype "passive"))
    )
    (net (code "46") (name "Net-(U$5-PadP$1)") (class "Default")
      (node (ref "U$5") (pin "P$1") (pinfunction "P$1_P$1") (pintype "passive"))
      (node (ref "U$5") (pin "P$2") (pinfunction "P$2_P$2") (pintype "passive"))
      (node (ref "U$5") (pin "P$3") (pinfunction "P$3_P$3") (pintype "passive"))
    )
    (net (code "47") (name "Net-(U$6-PadP$1)") (class "Default")
      (node (ref "U$6") (pin "P$1") (pinfunction "P$1_P$1") (pintype "passive"))
      (node (ref "U$6") (pin "P$2") (pinfunction "P$2_P$2") (pintype "passive"))
      (node (ref "U$6") (pin "P$3") (pinfunction "P$3_P$3") (pintype "passive"))
    )
    (net (code "48") (name "Net-(U$7-PadP$1)") (class "Default")
      (node (ref "U$7") (pin "P$1") (pinfunction "P$1_P$1") (pintype "passive"))
      (node (ref "U$7") (pin "P$2") (pinfunction "P$2_P$2") (pintype "passive"))
      (node (ref "U$7") (pin "P$3") (pinfunction "P$3_P$3") (pintype "passive"))
    )
    (net (code "49") (name "Net-(U$8-PadP$1)") (class "Default")
      (node (ref "U$8") (pin "P$1") (pinfunction "P$1_P$1") (pintype "passive"))
      (node (ref "U$8") (pin "P$2") (pinfunction "P$2_P$2") (pintype "passive"))
      (node (ref "U$8") (pin "P$3") (pinfunction "P$3_P$3") (pintype "passive"))
    )
    (net (code "50") (name "Net-(U$9-PadP$1)") (class "Default")
      (node (ref "U$9") (pin "P$1") (pinfunction "P$1_P$1") (pintype "passive"))
      (node (ref "U$9") (pin "P$2") (pinfunction "P$2_P$2") (pintype "passive"))
      (node (ref "U$9") (pin "P$3") (pinfunction "P$3_P$3") (pintype "passive"))
    )
    (net (code "51") (name "Net-(U$10-PadP$1)") (class "Default")
      (node (ref "U$10") (pin "P$1") (pinfunction "P$1_P$1") (pintype "passive"))
      (node (ref "U$10") (pin "P$2") (pinfunction "P$2_P$2") (pintype "passive"))
      (node (ref "U$10") (pin "P$3") (pinfunction "P$3_P$3") (pintype "passive"))
    )
    (net (code "52") (name "Net-(U$11-PadP$1)") (class "Default")
      (node (ref "U$11") (pin "P$1") (pinfunction "P$1_P$1") (pintype "passive"))
      (node (ref "U$11") (pin "P$2") (pinfunction "P$2_P$2") (pintype "passive"))
      (node (ref "U$11") (pin "P$3") (pinfunction "P$3_P$3") (pintype "passive"))
    )
    (net (code "53") (name "Net-(U$12-PadP$1)") (class "Default")
      (node (ref "U$12") (pin "P$1") (pinfunction "P$1_P$1") (pintype "passive"))
      (node (ref "U$12") (pin "P$2") (pinfunction "P$2_P$2") (pintype "passive"))
      (node (ref "U$12") (pin "P$3") (pinfunction "P$3_P$3") (pintype "passive"))
    )
    (net (code "54") (name "Net-(U$13-PadP$1)") (class "Default")
      (node (ref "U$13") (pin "P$1") (pinfunction "P$1_P$1") (pintype "passive"))
      (node (ref "U$13") (pin "P$2") (pinfunction "P$2_P$2") (pintype "passive"))
      (node (ref "U$13") (pin "P$3") (pinfunction "P$3_P$3") (pintype "passive"))
    )
    (net (code "55") (name "Net-(U$14-PadP$1)") (class "Default")
      (node (ref "U$14") (pin "P$1") (pinfunction "P$1_P$1") (pintype "passive"))
      (node (ref "U$14") (pin "P$2") (pinfunction "P$2_P$2") (pintype "passive"))
      (node (ref "U$14") (pin "P$3") (pinfunction "P$3_P$3") (pintype "passive"))
    )
    (net (code "56") (name "Net-(U$15-PadP$1)") (class "Default")
      (node (ref "U$15") (pin "P$1") (pinfunction "P$1_P$1") (pintype "passive"))
      (node (ref "U$15") (pin "P$2") (pinfunction "P$2_P$2") (pintype "passive"))
      (node (ref "U$15") (pin "P$3") (pinfunction "P$3_P$3") (pintype "passive"))
    )
    (net (code "57") (name "Net-(U$16-PadP$1)") (class "Default")
      (node (ref "U$16") (pin "P$1") (pinfunction "P$1_P$1") (pintype "passive"))
      (node (ref "U$16") (pin "P$2") (pinfunction "P$2_P$2") (pintype "passive"))
      (node (ref "U$16") (pin "P$3") (pinfunction "P$3_P$3") (pintype "passive"))
    )
    (net (code "58") (name "Net-(U$17-PadP$1)") (class "Default")
      (node (ref "U$17") (pin "P$1") (pinfunction "P$1_P$1") (pintype "passive"))
      (node (ref "U$17") (pin "P$2") (pinfunction "P$2_P$2") (pintype "passive"))
      (node (ref "U$17") (pin "P$3") (pinfunction "P$3_P$3") (pintype "passive"))
    )
    (net (code "59") (name "Net-(U$18-PadP$1)") (class "Default")
      (node (ref "U$18") (pin "P$1") (pinfunction "P$1_P$1") (pintype "passive"))
      (node (ref "U$18") (pin "P$2") (pinfunction "P$2_P$2") (pintype "passive"))
      (node (ref "U$18") (pin "P$3") (pinfunction "P$3_P$3") (pintype "passive"))
    )
    (net (code "60") (name "Net-(U$19-PadP$1)") (class "Default")
      (node (ref "U$19") (pin "P$1") (pinfunction "P$1_P$1") (pintype "passive"))
      (node (ref "U$19") (pin "P$2") (pinfunction "P$2_P$2") (pintype "passive"))
      (node (ref "U$19") (pin "P$3") (pinfunction "P$3_P$3") (pintype "passive"))
    )
    (net (code "61") (name "Net-(U$20-PadP$1)") (class "Default")
      (node (ref "U$20") (pin "P$1") (pinfunction "P$1_P$1") (pintype "passive"))
      (node (ref "U$20") (pin "P$2") (pinfunction "P$2_P$2") (pintype "passive"))
      (node (ref "U$20") (pin "P$3") (pinfunction "P$3_P$3") (pintype "passive"))
    )
    (net (code "62") (name "Net-(U$21-PadP$1)") (class "Default")
      (node (ref "U$21") (pin "P$1") (pinfunction "P$1_P$1") (pintype "passive"))
      (node (ref "U$21") (pin "P$2") (pinfunction "P$2_P$2") (pintype "passive"))
      (node (ref "U$21") (pin "P$3") (pinfunction "P$3_P$3") (pintype "passive"))
    )
    (net (code "63") (name "Net-(U$22-PadP$1)") (class "Default")
      (node (ref "U$22") (pin "P$1") (pinfunction "P$1_P$1") (pintype "passive"))
      (node (ref "U$22") (pin "P$2") (pinfunction "P$2_P$2") (pintype "passive"))
      (node (ref "U$22") (pin "P$3") (pinfunction "P$3_P$3") (pintype "passive"))
    )
    (net (code "64") (name "Net-(U$34-PadP$1)") (class "Default")
      (node (ref "U$34") (pin "P$1") (pinfunction "P$1_P$1") (pintype "passive"))
      (node (ref "U$34") (pin "P$2") (pinfunction "P$2_P$2") (pintype "passive"))
      (node (ref "U$34") (pin "P$3") (pinfunction "P$3_P$3") (pintype "passive"))
    )
    (net (code "65") (name "Net-(U$35-PadP$2)") (class "Default")
      (node (ref "U$35") (pin "P$2") (pinfunction "P$2_P$2") (pintype "passive"))
      (node (ref "U$35") (pin "P$3") (pinfunction "P$3_P$3") (pintype "passive"))
      (node (ref "U$35") (pin "P$4") (pinfunction "P$4_P$4") (pintype "passive"))
    )
    (net (code "66") (name "Net-(U$36-PadP$2)") (class "Default")
      (node (ref "U$36") (pin "P$2") (pinfunction "P$2_P$2") (pintype "passive"))
      (node (ref "U$36") (pin "P$3") (pinfunction "P$3_P$3") (pintype "passive"))
      (node (ref "U$36") (pin "P$4") (pinfunction "P$4_P$4") (pintype "passive"))
    )
    (net (code "67") (name "Net-(U$37-PadP$1)") (class "Default")
      (node (ref "U$37") (pin "P$1") (pinfunction "P$1_P$1") (pintype "passive"))
      (node (ref "U$37") (pin "P$2") (pinfunction "P$2_P$2") (pintype "passive"))
      (node (ref "U$37") (pin "P$3") (pinfunction "P$3_P$3") (pintype "passive"))
    )
    (net (code "68") (name "Net-(U$64-PadP$1)") (class "Default")
      (node (ref "U$64") (pin "P$1") (pinfunction "P$1_P$1") (pintype "passive"))
      (node (ref "U$67") (pin "P$1") (pinfunction "P$1_P$1") (pintype "passive"))
      (node (ref "U$68") (pin "P$1") (pinfunction "P$1_P$1") (pintype "passive"))
    )
    (net (code "69") (name "Net-(U$64-PadP$2)") (class "Default")
      (node (ref "U$64") (pin "P$2") (pinfunction "P$2_P$2") (pintype "passive"))
      (node (ref "U$67") (pin "P$2") (pinfunction "P$2_P$2") (pintype "passive"))
      (node (ref "U$68") (pin "P$2") (pinfunction "P$2_P$2") (pintype "passive"))
    )
    (net (code "70") (name "Net-(U$64-PadP$3)") (class "Default")
      (node (ref "U$64") (pin "P$3") (pinfunction "P$3_P$3") (pintype "passive"))
      (node (ref "U$67") (pin "P$3") (pinfunction "P$3_P$3") (pintype "passive"))
      (node (ref "U$68") (pin "P$3") (pinfunction "P$3_P$3") (pintype "passive"))
    )
    (net (code "71") (name "Net-(U$64-PadP$4)") (class "Default")
      (node (ref "U$64") (pin "P$4") (pinfunction "P$4_P$4") (pintype "passive"))
      (node (ref "U$67") (pin "P$4") (pinfunction "P$4_P$4") (pintype "passive"))
      (node (ref "U$68") (pin "P$4") (pinfunction "P$4_P$4") (pintype "passive"))
    )
    (net (code "72") (name "Net-(U$65-PadP$1)") (class "Default")
      (node (ref "U$65") (pin "P$1") (pinfunction "P$1_P$1") (pintype "passive"))
      (node (ref "U$66") (pin "P$1") (pinfunction "P$1_P$1") (pintype "passive"))
      (node (ref "U$69") (pin "P$1") (pinfunction "P$1_P$1") (pintype "passive"))
    )
    (net (code "73") (name "Net-(U$65-PadP$2)") (class "Default")
      (node (ref "U$65") (pin "P$2") (pinfunction "P$2_P$2") (pintype "passive"))
      (node (ref "U$66") (pin "P$2") (pinfunction "P$2_P$2") (pintype "passive"))
      (node (ref "U$69") (pin "P$2") (pinfunction "P$2_P$2") (pintype "passive"))
    )
    (net (code "74") (name "Net-(U$65-PadP$3)") (class "Default")
      (node (ref "U$65") (pin "P$3") (pinfunction "P$3_P$3") (pintype "passive"))
      (node (ref "U$66") (pin "P$3") (pinfunction "P$3_P$3") (pintype "passive"))
      (node (ref "U$69") (pin "P$3") (pinfunction "P$3_P$3") (pintype "passive"))
    )
    (net (code "75") (name "Net-(U$65-PadP$4)") (class "Default")
      (node (ref "U$65") (pin "P$4") (pinfunction "P$4_P$4") (pintype "passive"))
      (node (ref "U$66") (pin "P$4") (pinfunction "P$4_P$4") (pintype "passive"))
      (node (ref "U$69") (pin "P$4") (pinfunction "P$4_P$4") (pintype "passive"))
    )
    (net (code "76") (name "Net-(U$76-PadP$1)") (class "Default")
      (node (ref "U$76") (pin "P$1") (pinfunction "P$1_P$1") (pintype "passive"))
      (node (ref "U$76") (pin "P$2") (pinfunction "P$2_P$2") (pintype "passive"))
      (node (ref "U$76") (pin "P$3") (pinfunction "P$3_P$3") (pintype "passive"))
    )
    (net (code "77") (name "Net-(U$81-PadP$1)") (class "Default")
      (node (ref "U$81") (pin "P$1") (pinfunction "P$1_P$1") (pintype "passive"))
      (node (ref "U$81") (pin "P$2") (pinfunction "P$2_P$2") (pintype "passive"))
      (node (ref "U$81") (pin "P$3") (pinfunction "P$3_P$3") (pintype "passive"))
    )
    (net (code "78") (name "Net-(U$88-PadP$1)") (class "Default")
      (node (ref "U$88") (pin "P$1") (pinfunction "P$1_P$1") (pintype "passive"))
      (node (ref "U$88") (pin "P$2") (pinfunction "P$2_P$2") (pintype "passive"))
      (node (ref "U$88") (pin "P$3") (pinfunction "P$3_P$3") (pintype "passive"))
    )
    (net (code "79") (name "Net-(U$89-PadP$1)") (class "Default")
      (node (ref "U$89") (pin "P$1") (pinfunction "P$1_P$1") (pintype "passive"))
      (node (ref "U$89") (pin "P$2") (pinfunction "P$2_P$2") (pintype "passive"))
      (node (ref "U$89") (pin "P$3") (pinfunction "P$3_P$3") (pintype "passive"))
    )
    (net (code "80") (name "Net-(U$96-PadP$1)") (class "Default")
      (node (ref "U$96") (pin "P$1") (pinfunction "P$1_P$1") (pintype "passive"))
      (node (ref "U$96") (pin "P$2") (pinfunction "P$2_P$2") (pintype "passive"))
      (node (ref "U$96") (pin "P$3") (pinfunction "P$3_P$3") (pintype "passive"))
    )
    (net (code "81") (name "Net-(U$99-PadP$1)") (class "Default")
      (node (ref "U$99") (pin "P$1") (pinfunction "P$1_P$1") (pintype "passive"))
      (node (ref "U$99") (pin "P$2") (pinfunction "P$2_P$2") (pintype "passive"))
      (node (ref "U$99") (pin "P$3") (pinfunction "P$3_P$3") (pintype "passive"))
    )
    (net (code "82") (name "V+") (class "Default")
      (node (ref "U$1") (pin "IVIN") (pinfunction "VIN_IVIN") (pintype "power_in"))
      (node (ref "U$1") (pin "OVIN") (pinfunction "VIN_OVIN") (pintype "power_in"))
      (node (ref "U$33") (pin "P$1") (pinfunction "P$1_P$1") (pintype "passive"))
    )
    (net (code "83") (name "unconnected-(U$1C-13-PadO1.13)") (class "Default")
      (node (ref "U$1") (pin "O1.13") (pinfunction "13_O1.13") (pintype "passive"))
    )
    (net (code "84") (name "unconnected-(U$1C-14-PadO1.14)") (class "Default")
      (node (ref "U$1") (pin "O1.14") (pinfunction "14_O1.14") (pintype "passive"))
    )
    (net (code "85") (name "unconnected-(U$1C-15-PadO1.15)") (class "Default")
      (node (ref "U$1") (pin "O1.15") (pinfunction "15_O1.15") (pintype "passive"))
    )
    (net (code "86") (name "unconnected-(U$1C-16-PadO1.16)") (class "Default")
      (node (ref "U$1") (pin "O1.16") (pinfunction "16_O1.16") (pintype "passive"))
    )
    (net (code "87") (name "unconnected-(U$1D-13-PadO2.13)") (class "Default")
      (node (ref "U$1") (pin "O2.13") (pinfunction "13_O2.13") (pintype "passive"))
    )
    (net (code "88") (name "unconnected-(U$1D-14-PadO2.14)") (class "Default")
      (node (ref "U$1") (pin "O2.14") (pinfunction "14_O2.14") (pintype "passive"))
    )
    (net (code "89") (name "unconnected-(U$1D-15-PadO2.15)") (class "Default")
      (node (ref "U$1") (pin "O2.15") (pinfunction "15_O2.15") (pintype "passive"))
    )
    (net (code "90") (name "unconnected-(U$1D-16-PadO2.16)") (class "Default")
      (node (ref "U$1") (pin "O2.16") (pinfunction "16_O2.16") (pintype "passive"))
    )
    (net (code "91") (name "unconnected-(U$38-PadP$1)") (class "Default")
      (node (ref "U$38") (pin "P$1") (pinfunction "P$1_P$1") (pintype "passive"))
    )
    (net (code "92") (name "unconnected-(U$38-PadP$2)") (class "Default")
      (node (ref "U$38") (pin "P$2") (pinfunction "P$2_P$2") (pintype "passive"))
    )
    (net (code "93") (name "unconnected-(U$38-PadP$3)") (class "Default")
      (node (ref "U$38") (pin "P$3") (pinfunction "P$3_P$3") (pintype "passive"))
    )
    (net (code "94") (name "unconnected-(U$38-PadP$4)") (class "Default")
      (node (ref "U$38") (pin "P$4") (pinfunction "P$4_P$4") (pintype "passive"))
    )
    (net (code "95") (name "unconnected-(U$39-PadP$1)") (class "Default")
      (node (ref "U$39") (pin "P$1") (pinfunction "P$1_P$1") (pintype "passive"))
    )
    (net (code "96") (name "unconnected-(U$39-PadP$2)") (class "Default")
      (node (ref "U$39") (pin "P$2") (pinfunction "P$2_P$2") (pintype "passive"))
    )
    (net (code "97") (name "unconnected-(U$39-PadP$3)") (class "Default")
      (node (ref "U$39") (pin "P$3") (pinfunction "P$3_P$3") (pintype "passive"))
    )
    (net (code "98") (name "unconnected-(U$39-PadP$4)") (class "Default")
      (node (ref "U$39") (pin "P$4") (pinfunction "P$4_P$4") (pintype "passive"))
    )
    (net (code "99") (name "unconnected-(U$40-PadP$1)") (class "Default")
      (node (ref "U$40") (pin "P$1") (pinfunction "P$1_P$1") (pintype "passive"))
    )
    (net (code "100") (name "unconnected-(U$40-PadP$2)") (class "Default")
      (node (ref "U$40") (pin "P$2") (pinfunction "P$2_P$2") (pintype "passive"))
    )
    (net (code "101") (name "unconnected-(U$40-PadP$3)") (class "Default")
      (node (ref "U$40") (pin "P$3") (pinfunction "P$3_P$3") (pintype "passive"))
    )
    (net (code "102") (name "unconnected-(U$40-PadP$4)") (class "Default")
      (node (ref "U$40") (pin "P$4") (pinfunction "P$4_P$4") (pintype "passive"))
    )
    (net (code "103") (name "unconnected-(U$41-PadP$1)") (class "Default")
      (node (ref "U$41") (pin "P$1") (pinfunction "P$1_P$1") (pintype "passive"))
    )
    (net (code "104") (name "unconnected-(U$41-PadP$2)") (class "Default")
      (node (ref "U$41") (pin "P$2") (pinfunction "P$2_P$2") (pintype "passive"))
    )
    (net (code "105") (name "unconnected-(U$41-PadP$3)") (class "Default")
      (node (ref "U$41") (pin "P$3") (pinfunction "P$3_P$3") (pintype "passive"))
    )
    (net (code "106") (name "unconnected-(U$41-PadP$4)") (class "Default")
      (node (ref "U$41") (pin "P$4") (pinfunction "P$4_P$4") (pintype "passive"))
    )
    (net (code "107") (name "unconnected-(U$42-PadP$1)") (class "Default")
      (node (ref "U$42") (pin "P$1") (pinfunction "P$1_P$1") (pintype "passive"))
    )
    (net (code "108") (name "unconnected-(U$42-PadP$2)") (class "Default")
      (node (ref "U$42") (pin "P$2") (pinfunction "P$2_P$2") (pintype "passive"))
    )
    (net (code "109") (name "unconnected-(U$42-PadP$3)") (class "Default")
      (node (ref "U$42") (pin "P$3") (pinfunction "P$3_P$3") (pintype "passive"))
    )
    (net (code "110") (name "unconnected-(U$42-PadP$4)") (class "Default")
      (node (ref "U$42") (pin "P$4") (pinfunction "P$4_P$4") (pintype "passive"))
    )
    (net (code "111") (name "unconnected-(U$43-PadP$1)") (class "Default")
      (node (ref "U$43") (pin "P$1") (pinfunction "P$1_P$1") (pintype "passive"))
    )
    (net (code "112") (name "unconnected-(U$43-PadP$2)") (class "Default")
      (node (ref "U$43") (pin "P$2") (pinfunction "P$2_P$2") (pintype "passive"))
    )
    (net (code "113") (name "unconnected-(U$43-PadP$3)") (class "Default")
      (node (ref "U$43") (pin "P$3") (pinfunction "P$3_P$3") (pintype "passive"))
    )
    (net (code "114") (name "unconnected-(U$43-PadP$4)") (class "Default")
      (node (ref "U$43") (pin "P$4") (pinfunction "P$4_P$4") (pintype "passive"))
    )
    (net (code "115") (name "unconnected-(U$44-PadP$1)") (class "Default")
      (node (ref "U$44") (pin "P$1") (pinfunction "P$1_P$1") (pintype "passive"))
    )
    (net (code "116") (name "unconnected-(U$44-PadP$2)") (class "Default")
      (node (ref "U$44") (pin "P$2") (pinfunction "P$2_P$2") (pintype "passive"))
    )
    (net (code "117") (name "unconnected-(U$44-PadP$3)") (class "Default")
      (node (ref "U$44") (pin "P$3") (pinfunction "P$3_P$3") (pintype "passive"))
    )
    (net (code "118") (name "unconnected-(U$44-PadP$4)") (class "Default")
      (node (ref "U$44") (pin "P$4") (pinfunction "P$4_P$4") (pintype "passive"))
    )
    (net (code "119") (name "unconnected-(U$45-PadP$1)") (class "Default")
      (node (ref "U$45") (pin "P$1") (pinfunction "P$1_P$1") (pintype "passive"))
    )
    (net (code "120") (name "unconnected-(U$45-PadP$2)") (class "Default")
      (node (ref "U$45") (pin "P$2") (pinfunction "P$2_P$2") (pintype "passive"))
    )
    (net (code "121") (name "unconnected-(U$45-PadP$3)") (class "Default")
      (node (ref "U$45") (pin "P$3") (pinfunction "P$3_P$3") (pintype "passive"))
    )
    (net (code "122") (name "unconnected-(U$45-PadP$4)") (class "Default")
      (node (ref "U$45") (pin "P$4") (pinfunction "P$4_P$4") (pintype "passive"))
    )
    (net (code "123") (name "unconnected-(U$46-PadP$1)") (class "Default")
      (node (ref "U$46") (pin "P$1") (pinfunction "P$1_P$1") (pintype "passive"))
    )
    (net (code "124") (name "unconnected-(U$46-PadP$2)") (class "Default")
      (node (ref "U$46") (pin "P$2") (pinfunction "P$2_P$2") (pintype "passive"))
    )
    (net (code "125") (name "unconnected-(U$46-PadP$3)") (class "Default")
      (node (ref "U$46") (pin "P$3") (pinfunction "P$3_P$3") (pintype "passive"))
    )
    (net (code "126") (name "unconnected-(U$46-PadP$4)") (class "Default")
      (node (ref "U$46") (pin "P$4") (pinfunction "P$4_P$4") (pintype "passive"))
    )
    (net (code "127") (name "unconnected-(U$47-PadP$1)") (class "Default")
      (node (ref "U$47") (pin "P$1") (pinfunction "P$1_P$1") (pintype "passive"))
    )
    (net (code "128") (name "unconnected-(U$47-PadP$2)") (class "Default")
      (node (ref "U$47") (pin "P$2") (pinfunction "P$2_P$2") (pintype "passive"))
    )
    (net (code "129") (name "unconnected-(U$47-PadP$3)") (class "Default")
      (node (ref "U$47") (pin "P$3") (pinfunction "P$3_P$3") (pintype "passive"))
    )
    (net (code "130") (name "unconnected-(U$47-PadP$4)") (class "Default")
      (node (ref "U$47") (pin "P$4") (pinfunction "P$4_P$4") (pintype "passive"))
    )
    (net (code "131") (name "unconnected-(U$48-PadP$1)") (class "Default")
      (node (ref "U$48") (pin "P$1") (pinfunction "P$1_P$1") (pintype "passive"))
    )
    (net (code "132") (name "unconnected-(U$48-PadP$2)") (class "Default")
      (node (ref "U$48") (pin "P$2") (pinfunction "P$2_P$2") (pintype "passive"))
    )
    (net (code "133") (name "unconnected-(U$48-PadP$3)") (class "Default")
      (node (ref "U$48") (pin "P$3") (pinfunction "P$3_P$3") (pintype "passive"))
    )
    (net (code "134") (name "unconnected-(U$48-PadP$4)") (class "Default")
      (node (ref "U$48") (pin "P$4") (pinfunction "P$4_P$4") (pintype "passive"))
    )
    (net (code "135") (name "unconnected-(U$49-PadP$1)") (class "Default")
      (node (ref "U$49") (pin "P$1") (pinfunction "P$1_P$1") (pintype "passive"))
    )
    (net (code "136") (name "unconnected-(U$49-PadP$2)") (class "Default")
      (node (ref "U$49") (pin "P$2") (pinfunction "P$2_P$2") (pintype "passive"))
    )
    (net (code "137") (name "unconnected-(U$49-PadP$3)") (class "Default")
      (node (ref "U$49") (pin "P$3") (pinfunction "P$3_P$3") (pintype "passive"))
    )
    (net (code "138") (name "unconnected-(U$49-PadP$4)") (class "Default")
      (node (ref "U$49") (pin "P$4") (pinfunction "P$4_P$4") (pintype "passive"))
    )
    (net (code "139") (name "unconnected-(U$50-PadP$1)") (class "Default")
      (node (ref "U$50") (pin "P$1") (pinfunction "P$1_P$1") (pintype "passive"))
    )
    (net (code "140") (name "unconnected-(U$50-PadP$2)") (class "Default")
      (node (ref "U$50") (pin "P$2") (pinfunction "P$2_P$2") (pintype "passive"))
    )
    (net (code "141") (name "unconnected-(U$50-PadP$3)") (class "Default")
      (node (ref "U$50") (pin "P$3") (pinfunction "P$3_P$3") (pintype "passive"))
    )
    (net (code "142") (name "unconnected-(U$50-PadP$4)") (class "Default")
      (node (ref "U$50") (pin "P$4") (pinfunction "P$4_P$4") (pintype "passive"))
    )
    (net (code "143") (name "unconnected-(U$51-PadP$1)") (class "Default")
      (node (ref "U$51") (pin "P$1") (pinfunction "P$1_P$1") (pintype "passive"))
    )
    (net (code "144") (name "unconnected-(U$51-PadP$2)") (class "Default")
      (node (ref "U$51") (pin "P$2") (pinfunction "P$2_P$2") (pintype "passive"))
    )
    (net (code "145") (name "unconnected-(U$51-PadP$3)") (class "Default")
      (node (ref "U$51") (pin "P$3") (pinfunction "P$3_P$3") (pintype "passive"))
    )
    (net (code "146") (name "unconnected-(U$51-PadP$4)") (class "Default")
      (node (ref "U$51") (pin "P$4") (pinfunction "P$4_P$4") (pintype "passive"))
    )
    (net (code "147") (name "unconnected-(U$52-PadP$1)") (class "Default")
      (node (ref "U$52") (pin "P$1") (pinfunction "P$1_P$1") (pintype "passive"))
    )
    (net (code "148") (name "unconnected-(U$52-PadP$2)") (class "Default")
      (node (ref "U$52") (pin "P$2") (pinfunction "P$2_P$2") (pintype "passive"))
    )
    (net (code "149") (name "unconnected-(U$52-PadP$3)") (class "Default")
      (node (ref "U$52") (pin "P$3") (pinfunction "P$3_P$3") (pintype "passive"))
    )
    (net (code "150") (name "unconnected-(U$52-PadP$4)") (class "Default")
      (node (ref "U$52") (pin "P$4") (pinfunction "P$4_P$4") (pintype "passive"))
    )
    (net (code "151") (name "unconnected-(U$53-PadP$1)") (class "Default")
      (node (ref "U$53") (pin "P$1") (pinfunction "P$1_P$1") (pintype "passive"))
    )
    (net (code "152") (name "unconnected-(U$53-PadP$2)") (class "Default")
      (node (ref "U$53") (pin "P$2") (pinfunction "P$2_P$2") (pintype "passive"))
    )
    (net (code "153") (name "unconnected-(U$53-PadP$3)") (class "Default")
      (node (ref "U$53") (pin "P$3") (pinfunction "P$3_P$3") (pintype "passive"))
    )
    (net (code "154") (name "unconnected-(U$53-PadP$4)") (class "Default")
      (node (ref "U$53") (pin "P$4") (pinfunction "P$4_P$4") (pintype "passive"))
    )
    (net (code "155") (name "unconnected-(U$54-PadP$1)") (class "Default")
      (node (ref "U$54") (pin "P$1") (pinfunction "P$1_P$1") (pintype "passive"))
    )
    (net (code "156") (name "unconnected-(U$54-PadP$2)") (class "Default")
      (node (ref "U$54") (pin "P$2") (pinfunction "P$2_P$2") (pintype "passive"))
    )
    (net (code "157") (name "unconnected-(U$54-PadP$3)") (class "Default")
      (node (ref "U$54") (pin "P$3") (pinfunction "P$3_P$3") (pintype "passive"))
    )
    (net (code "158") (name "unconnected-(U$54-PadP$4)") (class "Default")
      (node (ref "U$54") (pin "P$4") (pinfunction "P$4_P$4") (pintype "passive"))
    )
    (net (code "159") (name "unconnected-(U$55-PadP$1)") (class "Default")
      (node (ref "U$55") (pin "P$1") (pinfunction "P$1_P$1") (pintype "passive"))
    )
    (net (code "160") (name "unconnected-(U$55-PadP$2)") (class "Default")
      (node (ref "U$55") (pin "P$2") (pinfunction "P$2_P$2") (pintype "passive"))
    )
    (net (code "161") (name "unconnected-(U$55-PadP$3)") (class "Default")
      (node (ref "U$55") (pin "P$3") (pinfunction "P$3_P$3") (pintype "passive"))
    )
    (net (code "162") (name "unconnected-(U$55-PadP$4)") (class "Default")
      (node (ref "U$55") (pin "P$4") (pinfunction "P$4_P$4") (pintype "passive"))
    )
    (net (code "163") (name "unconnected-(U$56-PadP$1)") (class "Default")
      (node (ref "U$56") (pin "P$1") (pinfunction "P$1_P$1") (pintype "passive"))
    )
    (net (code "164") (name "unconnected-(U$56-PadP$2)") (class "Default")
      (node (ref "U$56") (pin "P$2") (pinfunction "P$2_P$2") (pintype "passive"))
    )
    (net (code "165") (name "unconnected-(U$56-PadP$3)") (class "Default")
      (node (ref "U$56") (pin "P$3") (pinfunction "P$3_P$3") (pintype "passive"))
    )
    (net (code "166") (name "unconnected-(U$56-PadP$4)") (class "Default")
      (node (ref "U$56") (pin "P$4") (pinfunction "P$4_P$4") (pintype "passive"))
    )
    (net (code "167") (name "unconnected-(U$57-PadP$1)") (class "Default")
      (node (ref "U$57") (pin "P$1") (pinfunction "P$1_P$1") (pintype "passive"))
    )
    (net (code "168") (name "unconnected-(U$57-PadP$2)") (class "Default")
      (node (ref "U$57") (pin "P$2") (pinfunction "P$2_P$2") (pintype "passive"))
    )
    (net (code "169") (name "unconnected-(U$57-PadP$3)") (class "Default")
      (node (ref "U$57") (pin "P$3") (pinfunction "P$3_P$3") (pintype "passive"))
    )
    (net (code "170") (name "unconnected-(U$57-PadP$4)") (class "Default")
      (node (ref "U$57") (pin "P$4") (pinfunction "P$4_P$4") (pintype "passive"))
    )
    (net (code "171") (name "unconnected-(U$58-PadP$1)") (class "Default")
      (node (ref "U$58") (pin "P$1") (pinfunction "P$1_P$1") (pintype "passive"))
    )
    (net (code "172") (name "unconnected-(U$58-PadP$2)") (class "Default")
      (node (ref "U$58") (pin "P$2") (pinfunction "P$2_P$2") (pintype "passive"))
    )
    (net (code "173") (name "unconnected-(U$58-PadP$3)") (class "Default")
      (node (ref "U$58") (pin "P$3") (pinfunction "P$3_P$3") (pintype "passive"))
    )
    (net (code "174") (name "unconnected-(U$58-PadP$4)") (class "Default")
      (node (ref "U$58") (pin "P$4") (pinfunction "P$4_P$4") (pintype "passive"))
    )
    (net (code "175") (name "unconnected-(U$59-PadP$1)") (class "Default")
      (node (ref "U$59") (pin "P$1") (pinfunction "P$1_P$1") (pintype "passive"))
    )
    (net (code "176") (name "unconnected-(U$59-PadP$2)") (class "Default")
      (node (ref "U$59") (pin "P$2") (pinfunction "P$2_P$2") (pintype "passive"))
    )
    (net (code "177") (name "unconnected-(U$59-PadP$3)") (class "Default")
      (node (ref "U$59") (pin "P$3") (pinfunction "P$3_P$3") (pintype "passive"))
    )
    (net (code "178") (name "unconnected-(U$59-PadP$4)") (class "Default")
      (node (ref "U$59") (pin "P$4") (pinfunction "P$4_P$4") (pintype "passive"))
    )
    (net (code "179") (name "unconnected-(U$60-PadP$1)") (class "Default")
      (node (ref "U$60") (pin "P$1") (pinfunction "P$1_P$1") (pintype "passive"))
    )
    (net (code "180") (name "unconnected-(U$60-PadP$2)") (class "Default")
      (node (ref "U$60") (pin "P$2") (pinfunction "P$2_P$2") (pintype "passive"))
    )
    (net (code "181") (name "unconnected-(U$60-PadP$3)") (class "Default")
      (node (ref "U$60") (pin "P$3") (pinfunction "P$3_P$3") (pintype "passive"))
    )
    (net (code "182") (name "unconnected-(U$60-PadP$4)") (class "Default")
      (node (ref "U$60") (pin "P$4") (pinfunction "P$4_P$4") (pintype "passive"))
    )
    (net (code "183") (name "unconnected-(U$61-PadP$1)") (class "Default")
      (node (ref "U$61") (pin "P$1") (pinfunction "P$1_P$1") (pintype "passive"))
    )
    (net (code "184") (name "unconnected-(U$61-PadP$2)") (class "Default")
      (node (ref "U$61") (pin "P$2") (pinfunction "P$2_P$2") (pintype "passive"))
    )
    (net (code "185") (name "unconnected-(U$61-PadP$3)") (class "Default")
      (node (ref "U$61") (pin "P$3") (pinfunction "P$3_P$3") (pintype "passive"))
    )
    (net (code "186") (name "unconnected-(U$61-PadP$4)") (class "Default")
      (node (ref "U$61") (pin "P$4") (pinfunction "P$4_P$4") (pintype "passive"))
    )
    (net (code "187") (name "unconnected-(U$62-PadP$1)") (class "Default")
      (node (ref "U$62") (pin "P$1") (pinfunction "P$1_P$1") (pintype "passive"))
    )
    (net (code "188") (name "unconnected-(U$62-PadP$2)") (class "Default")
      (node (ref "U$62") (pin "P$2") (pinfunction "P$2_P$2") (pintype "passive"))
    )
    (net (code "189") (name "unconnected-(U$62-PadP$3)") (class "Default")
      (node (ref "U$62") (pin "P$3") (pinfunction "P$3_P$3") (pintype "passive"))
    )
    (net (code "190") (name "unconnected-(U$62-PadP$4)") (class "Default")
      (node (ref "U$62") (pin "P$4") (pinfunction "P$4_P$4") (pintype "passive"))
    )
    (net (code "191") (name "unconnected-(U$63-PadP$1)") (class "Default")
      (node (ref "U$63") (pin "P$1") (pinfunction "P$1_P$1") (pintype "passive"))
    )
    (net (code "192") (name "unconnected-(U$63-PadP$2)") (class "Default")
      (node (ref "U$63") (pin "P$2") (pinfunction "P$2_P$2") (pintype "passive"))
    )
    (net (code "193") (name "unconnected-(U$63-PadP$3)") (class "Default")
      (node (ref "U$63") (pin "P$3") (pinfunction "P$3_P$3") (pintype "passive"))
    )
    (net (code "194") (name "unconnected-(U$63-PadP$4)") (class "Default")
      (node (ref "U$63") (pin "P$4") (pinfunction "P$4_P$4") (pintype "passive"))
    )
    (net (code "195") (name "unconnected-(U$70-PadP$1)") (class "Default")
      (node (ref "U$70") (pin "P$1") (pinfunction "P$1_P$1") (pintype "passive"))
    )
    (net (code "196") (name "unconnected-(U$70-PadP$2)") (class "Default")
      (node (ref "U$70") (pin "P$2") (pinfunction "P$2_P$2") (pintype "passive"))
    )
    (net (code "197") (name "unconnected-(U$70-PadP$3)") (class "Default")
      (node (ref "U$70") (pin "P$3") (pinfunction "P$3_P$3") (pintype "passive"))
    )
    (net (code "198") (name "unconnected-(U$70-PadP$4)") (class "Default")
      (node (ref "U$70") (pin "P$4") (pinfunction "P$4_P$4") (pintype "passive"))
    )
    (net (code "199") (name "unconnected-(U$71-PadP$1)") (class "Default")
      (node (ref "U$71") (pin "P$1") (pinfunction "P$1_P$1") (pintype "passive"))
    )
    (net (code "200") (name "unconnected-(U$71-PadP$2)") (class "Default")
      (node (ref "U$71") (pin "P$2") (pinfunction "P$2_P$2") (pintype "passive"))
    )
    (net (code "201") (name "unconnected-(U$71-PadP$3)") (class "Default")
      (node (ref "U$71") (pin "P$3") (pinfunction "P$3_P$3") (pintype "passive"))
    )
    (net (code "202") (name "unconnected-(U$71-PadP$4)") (class "Default")
      (node (ref "U$71") (pin "P$4") (pinfunction "P$4_P$4") (pintype "passive"))
    )
    (net (code "203") (name "unconnected-(U$72-PadP$1)") (class "Default")
      (node (ref "U$72") (pin "P$1") (pinfunction "P$1_P$1") (pintype "passive"))
    )
    (net (code "204") (name "unconnected-(U$72-PadP$2)") (class "Default")
      (node (ref "U$72") (pin "P$2") (pinfunction "P$2_P$2") (pintype "passive"))
    )
    (net (code "205") (name "unconnected-(U$72-PadP$3)") (class "Default")
      (node (ref "U$72") (pin "P$3") (pinfunction "P$3_P$3") (pintype "passive"))
    )
    (net (code "206") (name "unconnected-(U$72-PadP$4)") (class "Default")
      (node (ref "U$72") (pin "P$4") (pinfunction "P$4_P$4") (pintype "passive"))
    )
    (net (code "207") (name "unconnected-(U$73-PadP$1)") (class "Default")
      (node (ref "U$73") (pin "P$1") (pinfunction "P$1_P$1") (pintype "passive"))
    )
    (net (code "208") (name "unconnected-(U$73-PadP$2)") (class "Default")
      (node (ref "U$73") (pin "P$2") (pinfunction "P$2_P$2") (pintype "passive"))
    )
    (net (code "209") (name "unconnected-(U$73-PadP$3)") (class "Default")
      (node (ref "U$73") (pin "P$3") (pinfunction "P$3_P$3") (pintype "passive"))
    )
    (net (code "210") (name "unconnected-(U$73-PadP$4)") (class "Default")
      (node (ref "U$73") (pin "P$4") (pinfunction "P$4_P$4") (pintype "passive"))
    )
    (net (code "211") (name "unconnected-(U$74-PadP$1)") (class "Default")
      (node (ref "U$74") (pin "P$1") (pinfunction "P$1_P$1") (pintype "passive"))
    )
    (net (code "212") (name "unconnected-(U$74-PadP$2)") (class "Default")
      (node (ref "U$74") (pin "P$2") (pinfunction "P$2_P$2") (pintype "passive"))
    )
    (net (code "213") (name "unconnected-(U$74-PadP$3)") (class "Default")
      (node (ref "U$74") (pin "P$3") (pinfunction "P$3_P$3") (pintype "passive"))
    )
    (net (code "214") (name "unconnected-(U$74-PadP$4)") (class "Default")
      (node (ref "U$74") (pin "P$4") (pinfunction "P$4_P$4") (pintype "passive"))
    )
    (net (code "215") (name "unconnected-(U$75-PadP$1)") (class "Default")
      (node (ref "U$75") (pin "P$1") (pinfunction "P$1_P$1") (pintype "passive"))
    )
    (net (code "216") (name "unconnected-(U$75-PadP$2)") (class "Default")
      (node (ref "U$75") (pin "P$2") (pinfunction "P$2_P$2") (pintype "passive"))
    )
    (net (code "217") (name "unconnected-(U$75-PadP$3)") (class "Default")
      (node (ref "U$75") (pin "P$3") (pinfunction "P$3_P$3") (pintype "passive"))
    )
    (net (code "218") (name "unconnected-(U$75-PadP$4)") (class "Default")
      (node (ref "U$75") (pin "P$4") (pinfunction "P$4_P$4") (pintype "passive"))
    )
    (net (code "219") (name "unconnected-(U$76-PadP$4)") (class "Default")
      (node (ref "U$76") (pin "P$4") (pinfunction "P$4_P$4") (pintype "passive"))
    )
    (net (code "220") (name "unconnected-(U$81-PadP$4)") (class "Default")
      (node (ref "U$81") (pin "P$4") (pinfunction "P$4_P$4") (pintype "passive"))
    )
    (net (code "221") (name "unconnected-(U$82-PadP$1)") (class "Default")
      (node (ref "U$82") (pin "P$1") (pinfunction "P$1_P$1") (pintype "passive"))
    )
    (net (code "222") (name "unconnected-(U$82-PadP$2)") (class "Default")
      (node (ref "U$82") (pin "P$2") (pinfunction "P$2_P$2") (pintype "passive"))
    )
    (net (code "223") (name "unconnected-(U$82-PadP$3)") (class "Default")
      (node (ref "U$82") (pin "P$3") (pinfunction "P$3_P$3") (pintype "passive"))
    )
    (net (code "224") (name "unconnected-(U$82-PadP$4)") (class "Default")
      (node (ref "U$82") (pin "P$4") (pinfunction "P$4_P$4") (pintype "passive"))
    )
    (net (code "225") (name "unconnected-(U$83-PadP$1)") (class "Default")
      (node (ref "U$83") (pin "P$1") (pinfunction "P$1_P$1") (pintype "passive"))
    )
    (net (code "226") (name "unconnected-(U$83-PadP$2)") (class "Default")
      (node (ref "U$83") (pin "P$2") (pinfunction "P$2_P$2") (pintype "passive"))
    )
    (net (code "227") (name "unconnected-(U$83-PadP$3)") (class "Default")
      (node (ref "U$83") (pin "P$3") (pinfunction "P$3_P$3") (pintype "passive"))
    )
    (net (code "228") (name "unconnected-(U$83-PadP$4)") (class "Default")
      (node (ref "U$83") (pin "P$4") (pinfunction "P$4_P$4") (pintype "passive"))
    )
    (net (code "229") (name "unconnected-(U$84-PadP$1)") (class "Default")
      (node (ref "U$84") (pin "P$1") (pinfunction "P$1_P$1") (pintype "passive"))
    )
    (net (code "230") (name "unconnected-(U$84-PadP$2)") (class "Default")
      (node (ref "U$84") (pin "P$2") (pinfunction "P$2_P$2") (pintype "passive"))
    )
    (net (code "231") (name "unconnected-(U$84-PadP$3)") (class "Default")
      (node (ref "U$84") (pin "P$3") (pinfunction "P$3_P$3") (pintype "passive"))
    )
    (net (code "232") (name "unconnected-(U$84-PadP$4)") (class "Default")
      (node (ref "U$84") (pin "P$4") (pinfunction "P$4_P$4") (pintype "passive"))
    )
    (net (code "233") (name "unconnected-(U$85-PadP$1)") (class "Default")
      (node (ref "U$85") (pin "P$1") (pinfunction "P$1_P$1") (pintype "passive"))
    )
    (net (code "234") (name "unconnected-(U$85-PadP$2)") (class "Default")
      (node (ref "U$85") (pin "P$2") (pinfunction "P$2_P$2") (pintype "passive"))
    )
    (net (code "235") (name "unconnected-(U$85-PadP$3)") (class "Default")
      (node (ref "U$85") (pin "P$3") (pinfunction "P$3_P$3") (pintype "passive"))
    )
    (net (code "236") (name "unconnected-(U$85-PadP$4)") (class "Default")
      (node (ref "U$85") (pin "P$4") (pinfunction "P$4_P$4") (pintype "passive"))
    )
    (net (code "237") (name "unconnected-(U$86-PadP$1)") (class "Default")
      (node (ref "U$86") (pin "P$1") (pinfunction "P$1_P$1") (pintype "passive"))
    )
    (net (code "238") (name "unconnected-(U$86-PadP$2)") (class "Default")
      (node (ref "U$86") (pin "P$2") (pinfunction "P$2_P$2") (pintype "passive"))
    )
    (net (code "239") (name "unconnected-(U$86-PadP$3)") (class "Default")
      (node (ref "U$86") (pin "P$3") (pinfunction "P$3_P$3") (pintype "passive"))
    )
    (net (code "240") (name "unconnected-(U$86-PadP$4)") (class "Default")
      (node (ref "U$86") (pin "P$4") (pinfunction "P$4_P$4") (pintype "passive"))
    )
    (net (code "241") (name "unconnected-(U$87-PadP$1)") (class "Default")
      (node (ref "U$87") (pin "P$1") (pinfunction "P$1_P$1") (pintype "passive"))
    )
    (net (code "242") (name "unconnected-(U$87-PadP$2)") (class "Default")
      (node (ref "U$87") (pin "P$2") (pinfunction "P$2_P$2") (pintype "passive"))
    )
    (net (code "243") (name "unconnected-(U$87-PadP$3)") (class "Default")
      (node (ref "U$87") (pin "P$3") (pinfunction "P$3_P$3") (pintype "passive"))
    )
    (net (code "244") (name "unconnected-(U$87-PadP$4)") (class "Default")
      (node (ref "U$87") (pin "P$4") (pinfunction "P$4_P$4") (pintype "passive"))
    )
    (net (code "245") (name "unconnected-(U$88-PadP$4)") (class "Default")
      (node (ref "U$88") (pin "P$4") (pinfunction "P$4_P$4") (pintype "passive"))
    )
    (net (code "246") (name "unconnected-(U$89-PadP$4)") (class "Default")
      (node (ref "U$89") (pin "P$4") (pinfunction "P$4_P$4") (pintype "passive"))
    )
    (net (code "247") (name "unconnected-(U$90-PadP$1)") (class "Default")
      (node (ref "U$90") (pin "P$1") (pinfunction "P$1_P$1") (pintype "passive"))
    )
    (net (code "248") (name "unconnected-(U$90-PadP$2)") (class "Default")
      (node (ref "U$90") (pin "P$2") (pinfunction "P$2_P$2") (pintype "passive"))
    )
    (net (code "249") (name "unconnected-(U$90-PadP$3)") (class "Default")
      (node (ref "U$90") (pin "P$3") (pinfunction "P$3_P$3") (pintype "passive"))
    )
    (net (code "250") (name "unconnected-(U$90-PadP$4)") (class "Default")
      (node (ref "U$90") (pin "P$4") (pinfunction "P$4_P$4") (pintype "passive"))
    )
    (net (code "251") (name "unconnected-(U$91-PadP$1)") (class "Default")
      (node (ref "U$91") (pin "P$1") (pinfunction "P$1_P$1") (pintype "passive"))
    )
    (net (code "252") (name "unconnected-(U$91-PadP$2)") (class "Default")
      (node (ref "U$91") (pin "P$2") (pinfunction "P$2_P$2") (pintype "passive"))
    )
    (net (code "253") (name "unconnected-(U$91-PadP$3)") (class "Default")
      (node (ref "U$91") (pin "P$3") (pinfunction "P$3_P$3") (pintype "passive"))
    )
    (net (code "254") (name "unconnected-(U$91-PadP$4)") (class "Default")
      (node (ref "U$91") (pin "P$4") (pinfunction "P$4_P$4") (pintype "passive"))
    )
    (net (code "255") (name "unconnected-(U$92-PadP$1)") (class "Default")
      (node (ref "U$92") (pin "P$1") (pinfunction "P$1_P$1") (pintype "passive"))
    )
    (net (code "256") (name "unconnected-(U$92-PadP$2)") (class "Default")
      (node (ref "U$92") (pin "P$2") (pinfunction "P$2_P$2") (pintype "passive"))
    )
    (net (code "257") (name "unconnected-(U$92-PadP$3)") (class "Default")
      (node (ref "U$92") (pin "P$3") (pinfunction "P$3_P$3") (pintype "passive"))
    )
    (net (code "258") (name "unconnected-(U$92-PadP$4)") (class "Default")
      (node (ref "U$92") (pin "P$4") (pinfunction "P$4_P$4") (pintype "passive"))
    )
    (net (code "259") (name "unconnected-(U$93-PadP$1)") (class "Default")
      (node (ref "U$93") (pin "P$1") (pinfunction "P$1_P$1") (pintype "passive"))
    )
    (net (code "260") (name "unconnected-(U$93-PadP$2)") (class "Default")
      (node (ref "U$93") (pin "P$2") (pinfunction "P$2_P$2") (pintype "passive"))
    )
    (net (code "261") (name "unconnected-(U$93-PadP$3)") (class "Default")
      (node (ref "U$93") (pin "P$3") (pinfunction "P$3_P$3") (pintype "passive"))
    )
    (net (code "262") (name "unconnected-(U$93-PadP$4)") (class "Default")
      (node (ref "U$93") (pin "P$4") (pinfunction "P$4_P$4") (pintype "passive"))
    )
    (net (code "263") (name "unconnected-(U$94-PadP$1)") (class "Default")
      (node (ref "U$94") (pin "P$1") (pinfunction "P$1_P$1") (pintype "passive"))
    )
    (net (code "264") (name "unconnected-(U$94-PadP$2)") (class "Default")
      (node (ref "U$94") (pin "P$2") (pinfunction "P$2_P$2") (pintype "passive"))
    )
    (net (code "265") (name "unconnected-(U$94-PadP$3)") (class "Default")
      (node (ref "U$94") (pin "P$3") (pinfunction "P$3_P$3") (pintype "passive"))
    )
    (net (code "266") (name "unconnected-(U$94-PadP$4)") (class "Default")
      (node (ref "U$94") (pin "P$4") (pinfunction "P$4_P$4") (pintype "passive"))
    )
    (net (code "267") (name "unconnected-(U$95-PadP$1)") (class "Default")
      (node (ref "U$95") (pin "P$1") (pinfunction "P$1_P$1") (pintype "passive"))
    )
    (net (code "268") (name "unconnected-(U$95-PadP$2)") (class "Default")
      (node (ref "U$95") (pin "P$2") (pinfunction "P$2_P$2") (pintype "passive"))
    )
    (net (code "269") (name "unconnected-(U$95-PadP$3)") (class "Default")
      (node (ref "U$95") (pin "P$3") (pinfunction "P$3_P$3") (pintype "passive"))
    )
    (net (code "270") (name "unconnected-(U$95-PadP$4)") (class "Default")
      (node (ref "U$95") (pin "P$4") (pinfunction "P$4_P$4") (pintype "passive"))
    )
    (net (code "271") (name "unconnected-(U$96-PadP$4)") (class "Default")
      (node (ref "U$96") (pin "P$4") (pinfunction "P$4_P$4") (pintype "passive"))
    )
    (net (code "272") (name "unconnected-(U$97-PadP$1)") (class "Default")
      (node (ref "U$97") (pin "P$1") (pinfunction "P$1_P$1") (pintype "passive"))
    )
    (net (code "273") (name "unconnected-(U$97-PadP$2)") (class "Default")
      (node (ref "U$97") (pin "P$2") (pinfunction "P$2_P$2") (pintype "passive"))
    )
    (net (code "274") (name "unconnected-(U$97-PadP$3)") (class "Default")
      (node (ref "U$97") (pin "P$3") (pinfunction "P$3_P$3") (pintype "passive"))
    )
    (net (code "275") (name "unconnected-(U$97-PadP$4)") (class "Default")
      (node (ref "U$97") (pin "P$4") (pinfunction "P$4_P$4") (pintype "passive"))
    )
    (net (code "276") (name "unconnected-(U$98-PadP$1)") (class "Default")
      (node (ref "U$98") (pin "P$1") (pinfunction "P$1_P$1") (pintype "passive"))
    )
    (net (code "277") (name "unconnected-(U$98-PadP$2)") (class "Default")
      (node (ref "U$98") (pin "P$2") (pinfunction "P$2_P$2") (pintype "passive"))
    )
    (net (code "278") (name "unconnected-(U$98-PadP$3)") (class "Default")
      (node (ref "U$98") (pin "P$3") (pinfunction "P$3_P$3") (pintype "passive"))
    )
    (net (code "279") (name "unconnected-(U$98-PadP$4)") (class "Default")
      (node (ref "U$98") (pin "P$4") (pinfunction "P$4_P$4") (pintype "passive"))
    )
    (net (code "280") (name "unconnected-(U$99-PadP$4)") (class "Default")
      (node (ref "U$99") (pin "P$4") (pinfunction "P$4_P$4") (pintype "passive"))
    )
    (net (code "281") (name "unconnected-(U$100-PadP$1)") (class "Default")
      (node (ref "U$100") (pin "P$1") (pinfunction "P$1_P$1") (pintype "passive"))
    )
    (net (code "282") (name "unconnected-(U$100-PadP$2)") (class "Default")
      (node (ref "U$100") (pin "P$2") (pinfunction "P$2_P$2") (pintype "passive"))
    )
    (net (code "283") (name "unconnected-(U$100-PadP$3)") (class "Default")
      (node (ref "U$100") (pin "P$3") (pinfunction "P$3_P$3") (pintype "passive"))
    )
    (net (code "284") (name "unconnected-(U$100-PadP$4)") (class "Default")
      (node (ref "U$100") (pin "P$4") (pinfunction "P$4_P$4") (pintype "passive"))
    )
    (net (code "285") (name "unconnected-(U$101-PadP$1)") (class "Default")
      (node (ref "U$101") (pin "P$1") (pinfunction "P$1_P$1") (pintype "passive"))
    )
    (net (code "286") (name "unconnected-(U$101-PadP$2)") (class "Default")
      (node (ref "U$101") (pin "P$2") (pinfunction "P$2_P$2") (pintype "passive"))
    )
    (net (code "287") (name "unconnected-(U$101-PadP$3)") (class "Default")
      (node (ref "U$101") (pin "P$3") (pinfunction "P$3_P$3") (pintype "passive"))
    )
    (net (code "288") (name "unconnected-(U$101-PadP$4)") (class "Default")
      (node (ref "U$101") (pin "P$4") (pinfunction "P$4_P$4") (pintype "passive"))
    )
    (net (code "289") (name "unconnected-(U$102-PadP$1)") (class "Default")
      (node (ref "U$102") (pin "P$1") (pinfunction "P$1_P$1") (pintype "passive"))
    )
    (net (code "290") (name "unconnected-(U$102-PadP$2)") (class "Default")
      (node (ref "U$102") (pin "P$2") (pinfunction "P$2_P$2") (pintype "passive"))
    )
    (net (code "291") (name "unconnected-(U$102-PadP$3)") (class "Default")
      (node (ref "U$102") (pin "P$3") (pinfunction "P$3_P$3") (pintype "passive"))
    )
    (net (code "292") (name "unconnected-(U$102-PadP$4)") (class "Default")
      (node (ref "U$102") (pin "P$4") (pinfunction "P$4_P$4") (pintype "passive"))
    )
    (net (code "293") (name "unconnected-(U$103-PadP$1)") (class "Default")
      (node (ref "U$103") (pin "P$1") (pinfunction "P$1_P$1") (pintype "passive"))
    )
    (net (code "294") (name "unconnected-(U$103-PadP$2)") (class "Default")
      (node (ref "U$103") (pin "P$2") (pinfunction "P$2_P$2") (pintype "passive"))
    )
    (net (code "295") (name "unconnected-(U$103-PadP$3)") (class "Default")
      (node (ref "U$103") (pin "P$3") (pinfunction "P$3_P$3") (pintype "passive"))
    )
    (net (code "296") (name "unconnected-(U$103-PadP$4)") (class "Default")
      (node (ref "U$103") (pin "P$4") (pinfunction "P$4_P$4") (pintype "passive"))
    )
    (net (code "297") (name "unconnected-(U$104-PadP$1)") (class "Default")
      (node (ref "U$104") (pin "P$1") (pinfunction "P$1_P$1") (pintype "passive"))
    )
    (net (code "298") (name "unconnected-(U$104-PadP$2)") (class "Default")
      (node (ref "U$104") (pin "P$2") (pinfunction "P$2_P$2") (pintype "passive"))
    )
    (net (code "299") (name "unconnected-(U$105-PadP$1)") (class "Default")
      (node (ref "U$105") (pin "P$1") (pinfunction "P$1_P$1") (pintype "passive"))
    )
    (net (code "300") (name "unconnected-(U$105-PadP$2)") (class "Default")
      (node (ref "U$105") (pin "P$2") (pinfunction "P$2_P$2") (pintype "passive"))
    )
    (net (code "301") (name "unconnected-(U$106-PadP$1)") (class "Default")
      (node (ref "U$106") (pin "P$1") (pinfunction "P$1_P$1") (pintype "passive"))
    )
    (net (code "302") (name "unconnected-(U$106-PadP$2)") (class "Default")
      (node (ref "U$106") (pin "P$2") (pinfunction "P$2_P$2") (pintype "passive"))
    )
    (net (code "303") (name "unconnected-(U$107-PadP$1)") (class "Default")
      (node (ref "U$107") (pin "P$1") (pinfunction "P$1_P$1") (pintype "passive"))
    )
    (net (code "304") (name "unconnected-(U$107-PadP$2)") (class "Default")
      (node (ref "U$107") (pin "P$2") (pinfunction "P$2_P$2") (pintype "passive"))
    )
  )
)
